# frontplatine_v0_1.net
KiCad netlist of a schematic drawn in EAGLE
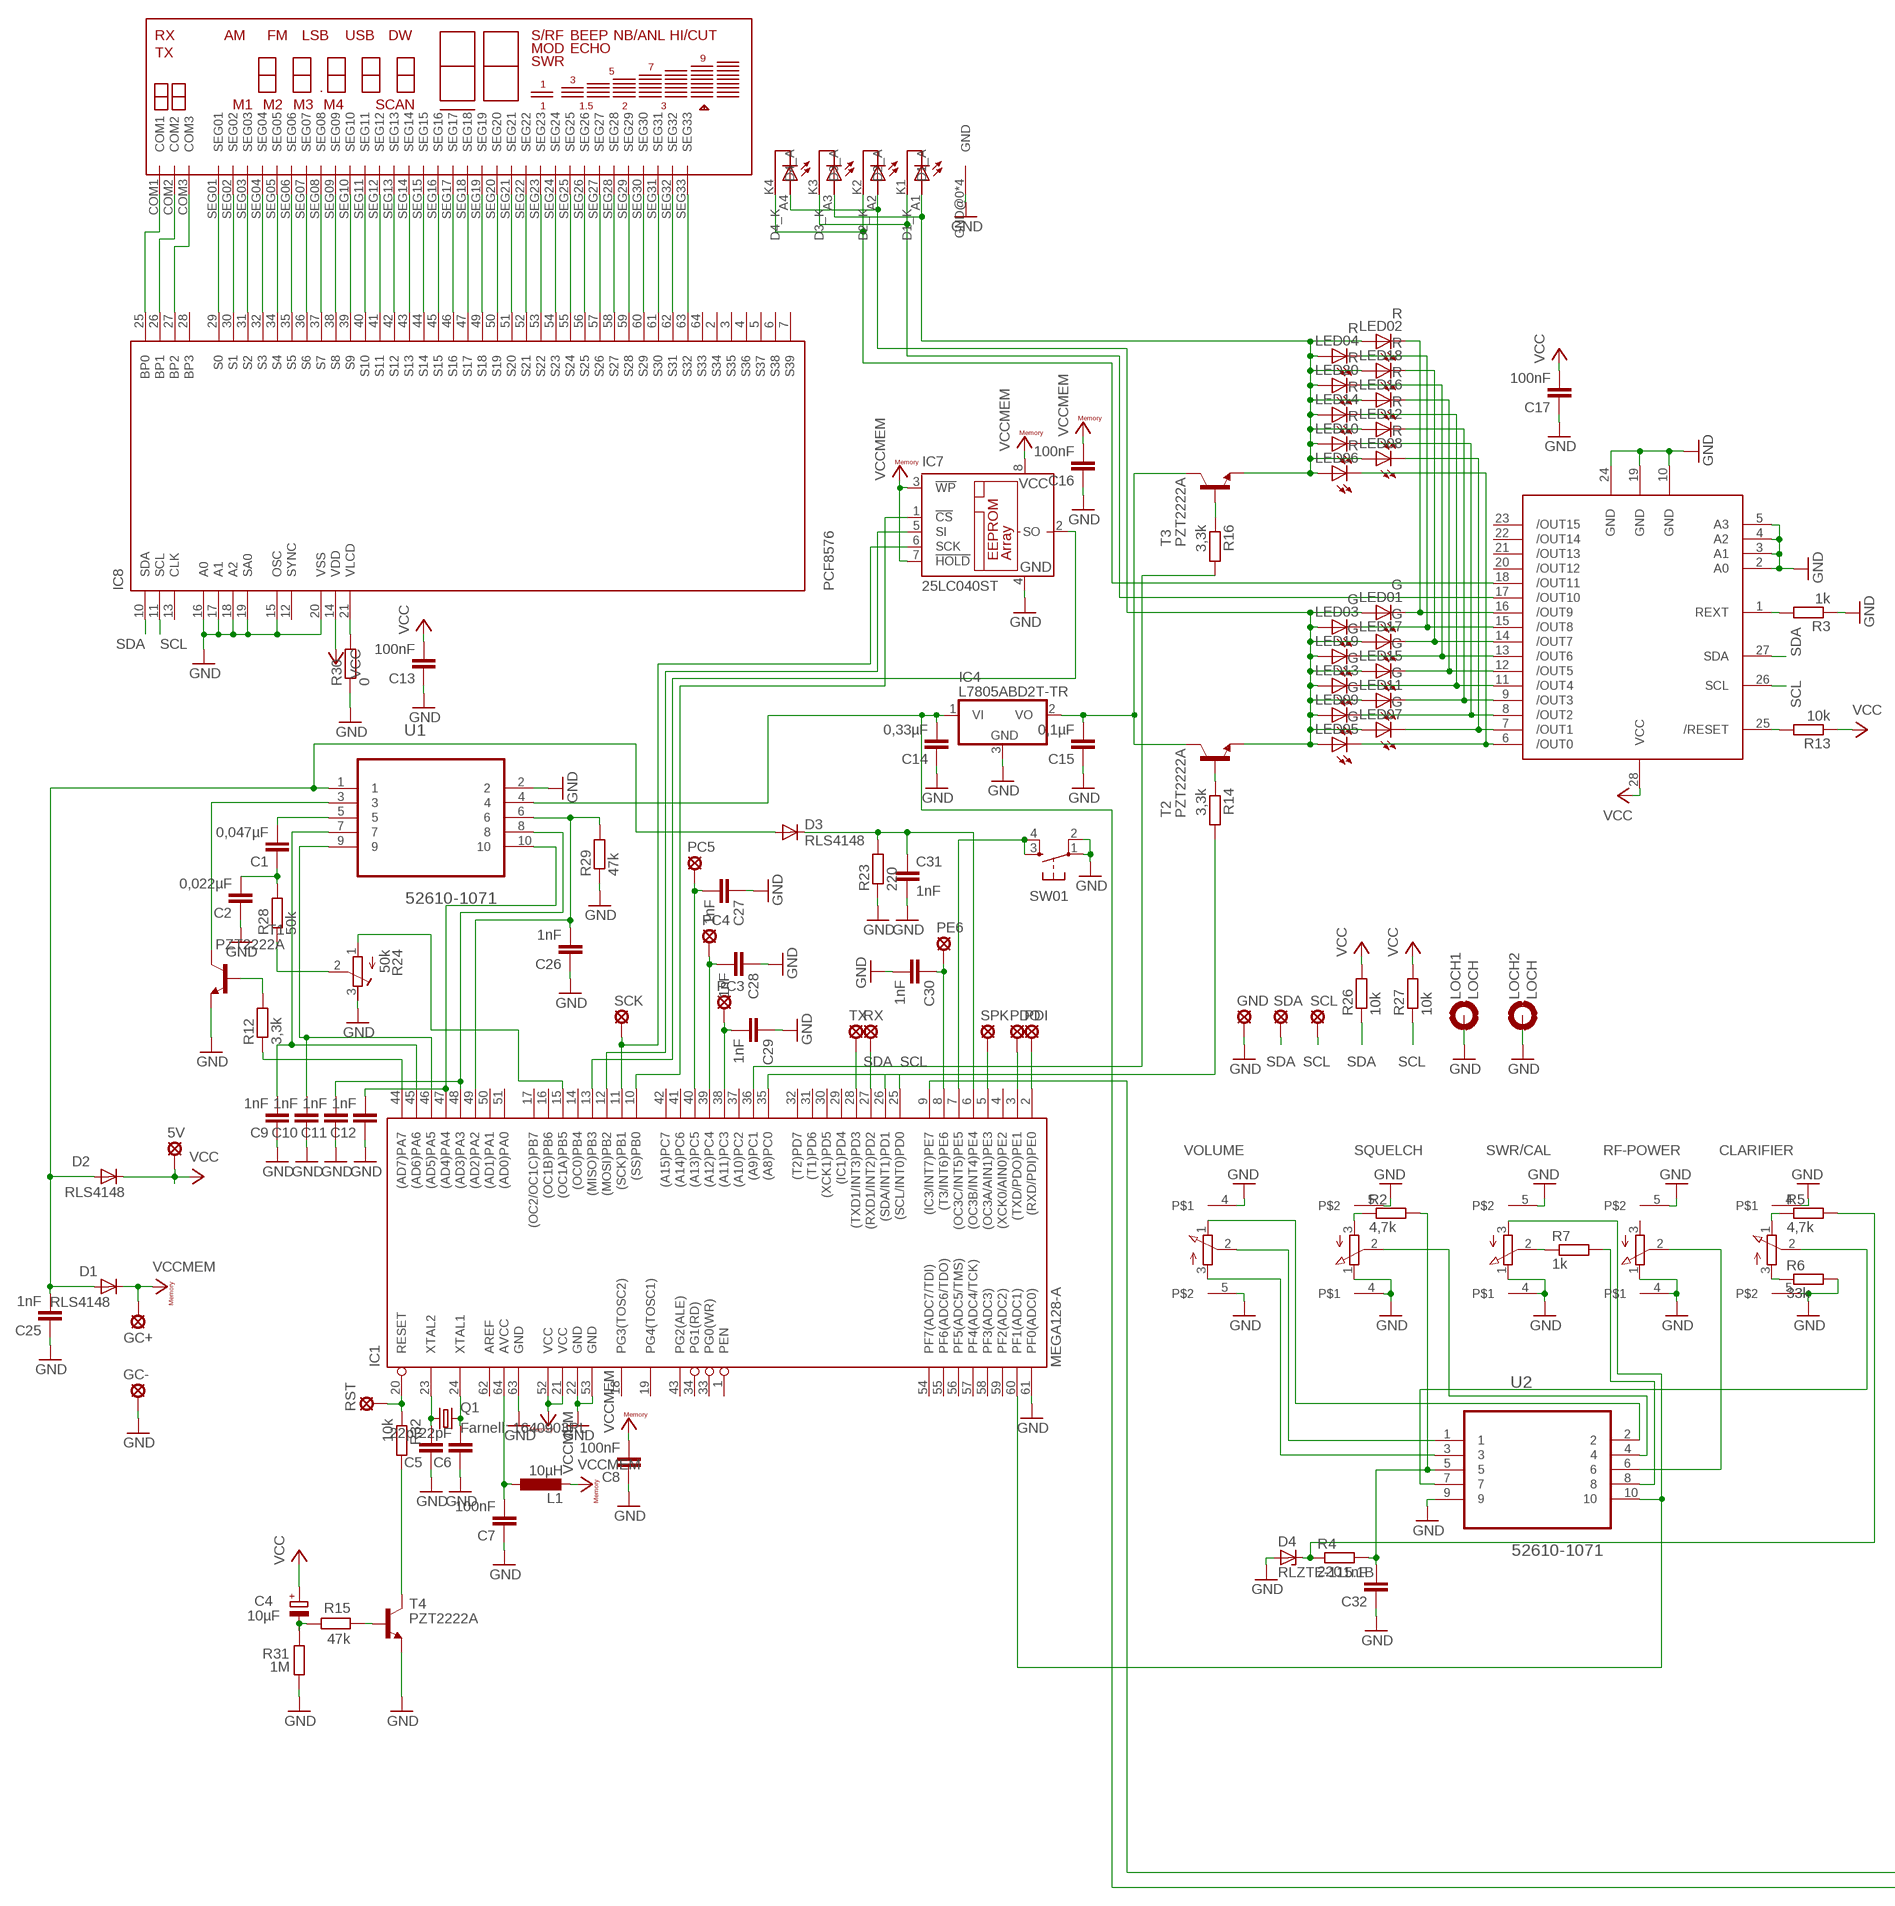
[diagram p0: schematic, sheet 1, part 1 of 2]
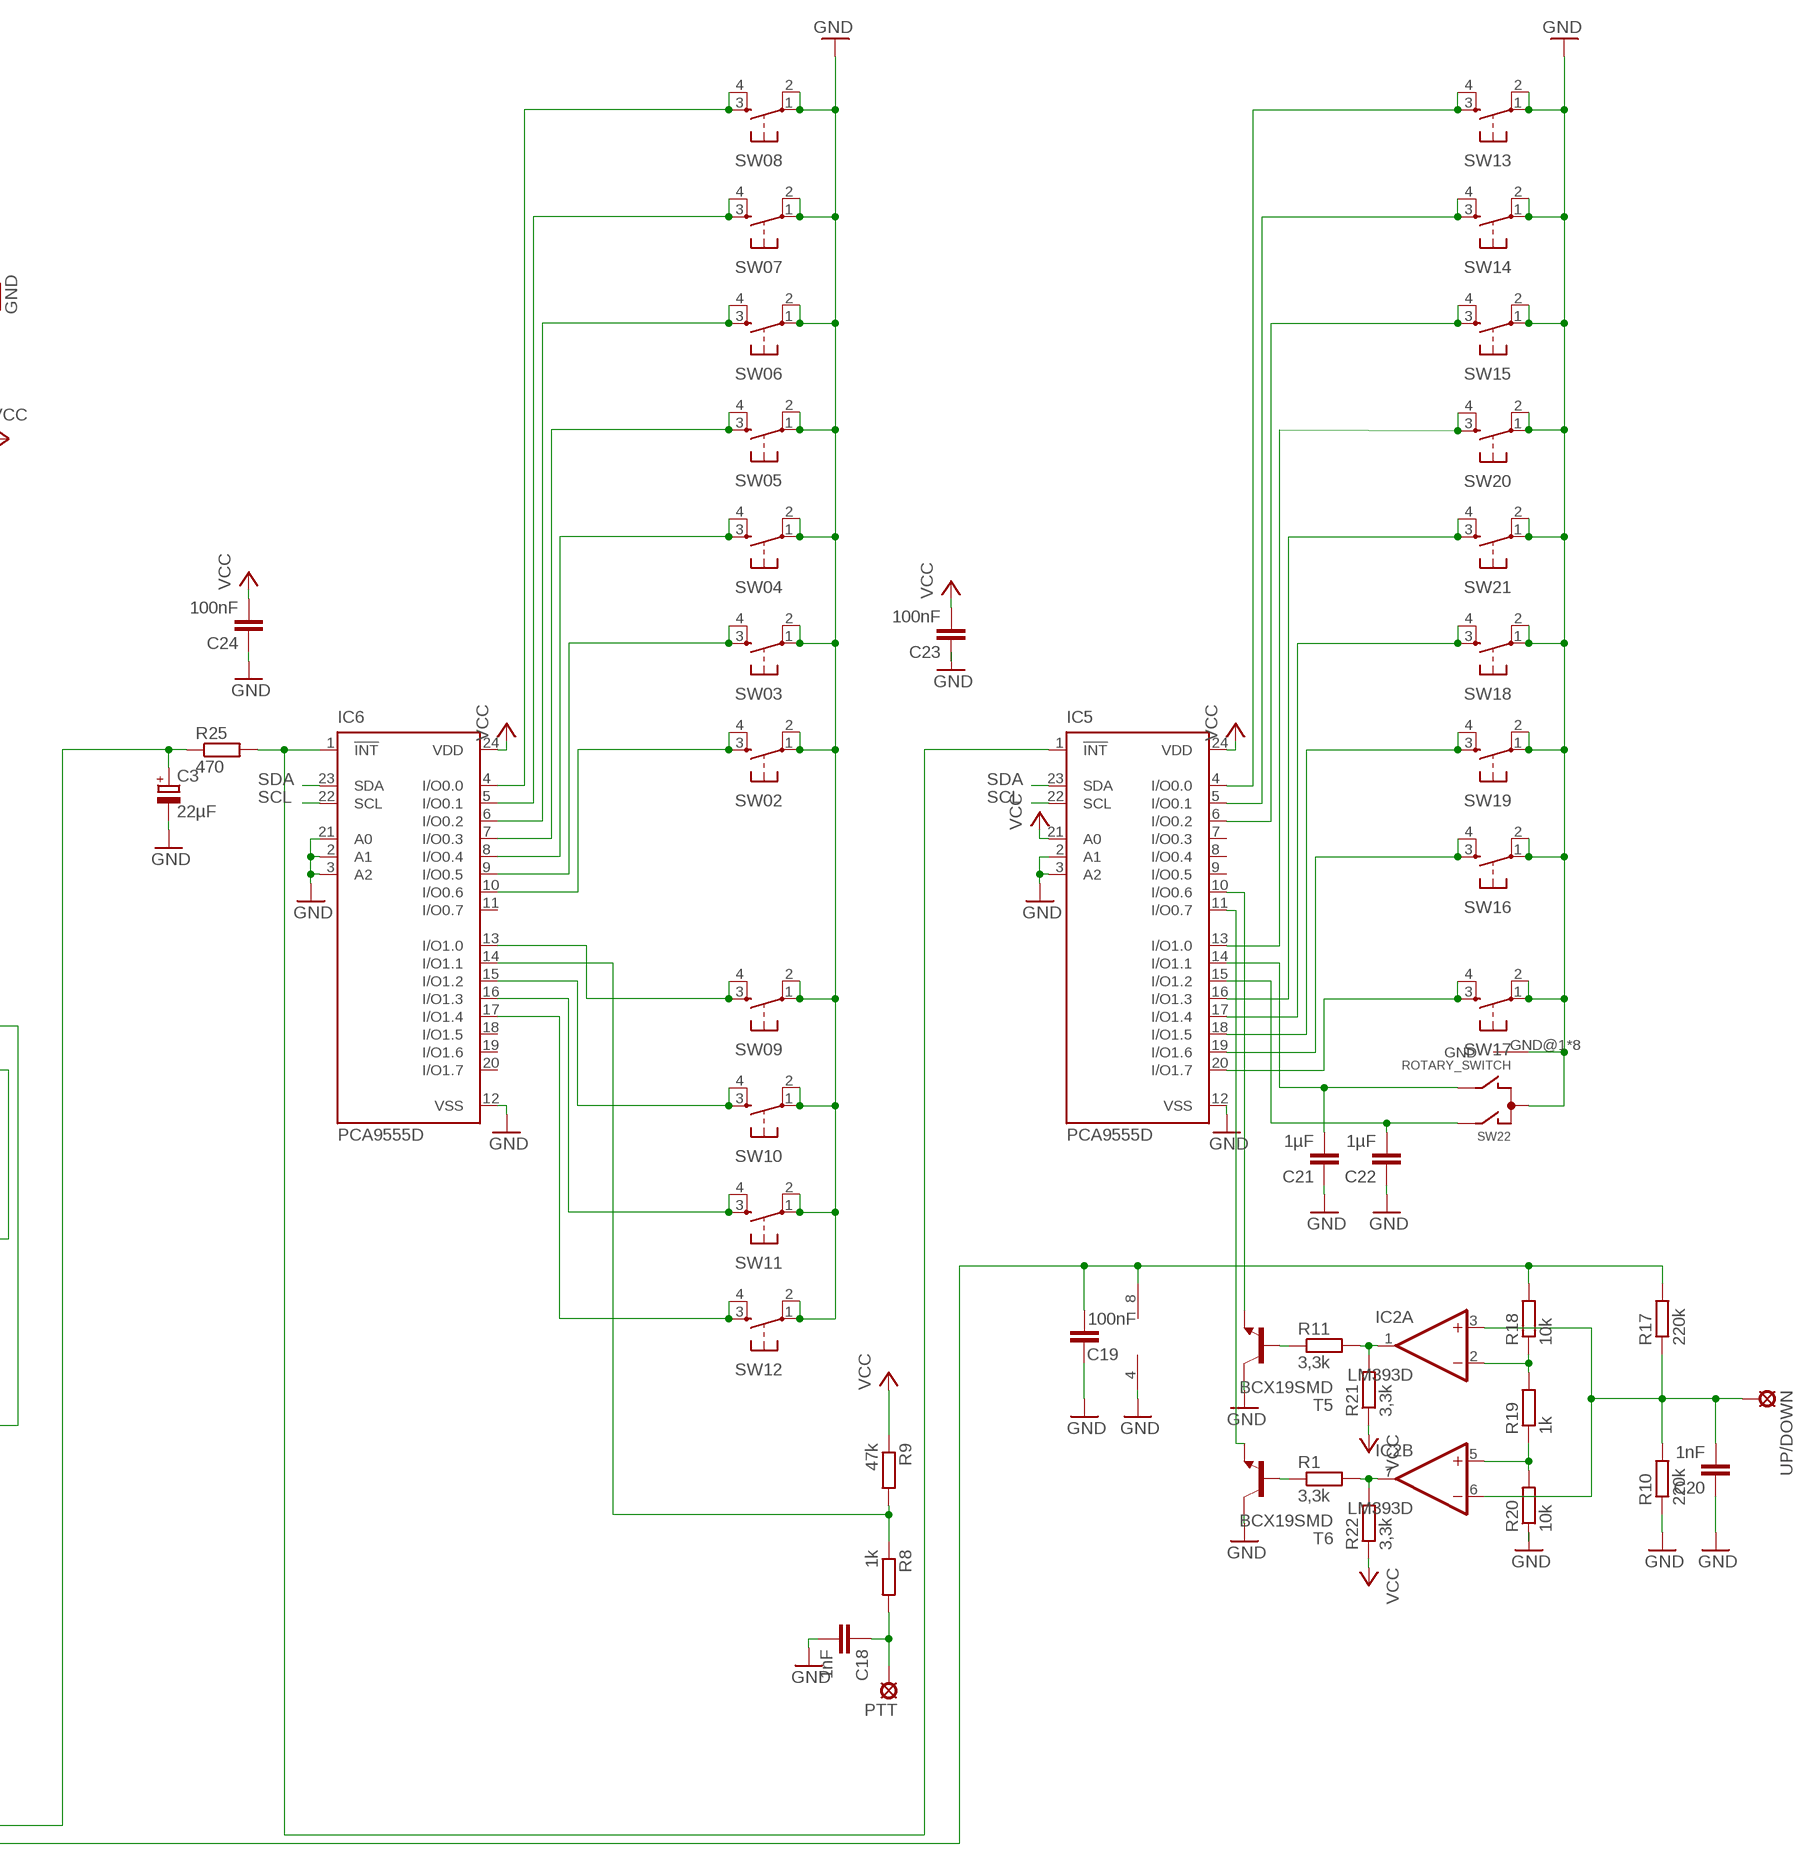
[diagram p1: schematic, sheet 1, part 2 of 2]

(export (version "E")
  (design (tool "Eeschema 10.0.6"))
  (components
    (comp (ref "5V")
      (value "SE11")
      (footprint "eagle-import:SE11")
      (libsource (lib "eagle-import") (part "SE11"))
    )
    (comp (ref "C1")
      (value "0,047µF")
      (footprint "eagle-import:C1206")
      (libsource (lib "eagle-import") (part "C-EUC1206"))
    )
    (comp (ref "C2")
      (value "0,022µF")
      (footprint "eagle-import:C1206")
      (libsource (lib "eagle-import") (part "resistor_C-EUC1206"))
    )
    (comp (ref "C3")
      (value "22µF")
      (footprint "eagle-import:CT3216")
      (libsource (lib "eagle-import") (part "CPOL-EUCT3216"))
    )
    (comp (ref "C4")
      (value "10µF")
      (footprint "eagle-import:CT3216")
      (libsource (lib "eagle-import") (part "CPOL-EUCT3216"))
    )
    (comp (ref "C5")
      (value "22pF")
      (footprint "eagle-import:C1206")
      (libsource (lib "eagle-import") (part "resistor_C-EUC1206"))
    )
    (comp (ref "C6")
      (value "22pF")
      (footprint "eagle-import:C1206")
      (libsource (lib "eagle-import") (part "resistor_C-EUC1206"))
    )
    (comp (ref "C7")
      (value "100nF")
      (footprint "eagle-import:C1206")
      (libsource (lib "eagle-import") (part "resistor_C-EUC1206"))
    )
    (comp (ref "C8")
      (value "100nF")
      (footprint "eagle-import:C1206")
      (libsource (lib "eagle-import") (part "resistor_C-EUC1206"))
    )
    (comp (ref "C9")
      (value "1nF")
      (footprint "eagle-import:C1206")
      (libsource (lib "eagle-import") (part "resistor_C-EUC1206"))
    )
    (comp (ref "C10")
      (value "1nF")
      (footprint "eagle-import:C1206")
      (libsource (lib "eagle-import") (part "resistor_C-EUC1206"))
    )
    (comp (ref "C11")
      (value "1nF")
      (footprint "eagle-import:C1206")
      (libsource (lib "eagle-import") (part "resistor_C-EUC1206"))
    )
    (comp (ref "C12")
      (value "1nF")
      (footprint "eagle-import:C1206")
      (libsource (lib "eagle-import") (part "resistor_C-EUC1206"))
    )
    (comp (ref "C13")
      (value "100nF")
      (footprint "eagle-import:C1206")
      (libsource (lib "eagle-import") (part "resistor_C-EUC1206"))
    )
    (comp (ref "C14")
      (value "0,33µF")
      (footprint "eagle-import:C1206")
      (libsource (lib "eagle-import") (part "resistor_C-EUC1206"))
    )
    (comp (ref "C15")
      (value "0,1µF")
      (footprint "eagle-import:C1206")
      (libsource (lib "eagle-import") (part "resistor_C-EUC1206"))
    )
    (comp (ref "C16")
      (value "100nF")
      (footprint "eagle-import:C1206")
      (libsource (lib "eagle-import") (part "resistor_C-EUC1206"))
    )
    (comp (ref "C17")
      (value "100nF")
      (footprint "eagle-import:C1206")
      (libsource (lib "eagle-import") (part "resistor_C-EUC1206"))
    )
    (comp (ref "C18")
      (value "1nF")
      (footprint "eagle-import:C1206")
      (libsource (lib "eagle-import") (part "resistor_C-EUC1206"))
    )
    (comp (ref "C19")
      (value "100nF")
      (footprint "eagle-import:C1206")
      (libsource (lib "eagle-import") (part "resistor_C-EUC1206"))
    )
    (comp (ref "C20")
      (value "1nF")
      (footprint "eagle-import:C1206")
      (libsource (lib "eagle-import") (part "resistor_C-EUC1206"))
    )
    (comp (ref "C21")
      (value "1µF")
      (footprint "eagle-import:C1206")
      (libsource (lib "eagle-import") (part "resistor_C-EUC1206"))
    )
    (comp (ref "C22")
      (value "1µF")
      (footprint "eagle-import:C1206")
      (libsource (lib "eagle-import") (part "resistor_C-EUC1206"))
    )
    (comp (ref "C23")
      (value "100nF")
      (footprint "eagle-import:C1206")
      (libsource (lib "eagle-import") (part "resistor_C-EUC1206"))
    )
    (comp (ref "C24")
      (value "100nF")
      (footprint "eagle-import:C1206")
      (libsource (lib "eagle-import") (part "resistor_C-EUC1206"))
    )
    (comp (ref "C25")
      (value "1nF")
      (footprint "eagle-import:C1206")
      (libsource (lib "eagle-import") (part "resistor_C-EUC1206"))
    )
    (comp (ref "C26")
      (value "1nF")
      (footprint "eagle-import:C1206")
      (libsource (lib "eagle-import") (part "resistor_C-EUC1206"))
    )
    (comp (ref "C27")
      (value "1nF")
      (footprint "eagle-import:C1206")
      (libsource (lib "eagle-import") (part "resistor_C-EUC1206"))
    )
    (comp (ref "C28")
      (value "1nF")
      (footprint "eagle-import:C1206")
      (libsource (lib "eagle-import") (part "resistor_C-EUC1206"))
    )
    (comp (ref "C29")
      (value "1nF")
      (footprint "eagle-import:C1206")
      (libsource (lib "eagle-import") (part "resistor_C-EUC1206"))
    )
    (comp (ref "C30")
      (value "1nF")
      (footprint "eagle-import:C1206")
      (libsource (lib "eagle-import") (part "resistor_C-EUC1206"))
    )
    (comp (ref "C31")
      (value "1nF")
      (footprint "eagle-import:C1206")
      (libsource (lib "eagle-import") (part "resistor_C-EUC1206"))
    )
    (comp (ref "C32")
      (value "1nF")
      (footprint "eagle-import:C1206")
      (libsource (lib "eagle-import") (part "resistor_C-EUC1206"))
    )
    (comp (ref "CLARIFIER")
      (value "POTI")
      (footprint "eagle-import:POTI")
      (libsource (lib "eagle-import") (part "POTI"))
    )
    (comp (ref "D1")
      (value "RLS4148")
      (footprint "eagle-import:SOD80C")
      (libsource (lib "eagle-import") (part "DIODE-SOD80C"))
    )
    (comp (ref "D2")
      (value "RLS4148")
      (footprint "eagle-import:SOD80C")
      (libsource (lib "eagle-import") (part "DIODE-SOD80C"))
    )
    (comp (ref "D3")
      (value "RLS4148")
      (footprint "eagle-import:SOD80C")
      (libsource (lib "eagle-import") (part "DIODE-SOD80C"))
    )
    (comp (ref "D4")
      (value "RLZTE-115.1B")
      (footprint "eagle-import:SOD80C")
      (libsource (lib "eagle-import") (part "ZENER-DIODESOD80C"))
    )
    (comp (ref "DISPLAY1")
      (value "DISPLAY")
      (footprint "eagle-import:DISPLAY")
      (libsource (lib "eagle-import") (part "DISPLAY"))
    )
    (comp (ref "GC+")
      (value "SE11")
      (footprint "eagle-import:SE11")
      (libsource (lib "eagle-import") (part "SE11"))
    )
    (comp (ref "GC-")
      (value "SE11")
      (footprint "eagle-import:SE11")
      (libsource (lib "eagle-import") (part "SE11"))
    )
    (comp (ref "GND")
      (value "SE11")
      (footprint "eagle-import:SE11")
      (libsource (lib "eagle-import") (part "SE11"))
    )
    (comp (ref "IC1")
      (value "MEGA128-A")
      (footprint "eagle-import:TQFP64")
      (fields (field (name "MPN") "ATMEGA128-16AU"))
      (libsource (lib "eagle-import") (part "MEGA128-A"))
    )
    (comp (ref "IC2")
      (value "LM393D")
      (footprint "eagle-import:SO08")
      (libsource (lib "eagle-import") (part "LM393D"))
    )
    (comp (ref "IC3")
      (value "TLC59116")
      (footprint "eagle-import:TSSOP28")
      (libsource (lib "eagle-import") (part "TLC59116"))
    )
    (comp (ref "IC4")
      (value "L7805ABD2T-TR")
      (footprint "eagle-import:TO252")
      (libsource (lib "eagle-import") (part "78DT05"))
    )
    (comp (ref "IC5")
      (value "PCA9555D")
      (footprint "eagle-import:SO24")
      (fields (field (name "MPN") "PCA9555DW"))
      (libsource (lib "eagle-import") (part "PCA9555D"))
    )
    (comp (ref "IC6")
      (value "PCA9555D")
      (footprint "eagle-import:SO24")
      (fields (field (name "MPN") "PCA9555DW"))
      (libsource (lib "eagle-import") (part "PCA9555D"))
    )
    (comp (ref "IC7")
      (value "25LC040ST")
      (footprint "eagle-import:TSSOP8")
      (fields (field (name "MF") "MICROCHIP") (field (name "MPN") "25LC040A-I/ST"))
      (libsource (lib "eagle-import") (part "25STLC040"))
    )
    (comp (ref "IC8")
      (value "PCF8576")
      (footprint "eagle-import:64LQFP")
      (libsource (lib "eagle-import") (part "PCF8576"))
    )
    (comp (ref "L1")
      (value "10µH")
      (footprint "eagle-import:L1812")
      (libsource (lib "eagle-import") (part "L-EUL1812"))
    )
    (comp (ref "LED01")
      (value "G")
      (footprint "eagle-import:CHIPLED_1206")
      (libsource (lib "eagle-import") (part "LEDCHIPLED_1206"))
    )
    (comp (ref "LED02")
      (value "R")
      (footprint "eagle-import:CHIPLED_1206")
      (libsource (lib "eagle-import") (part "LEDCHIPLED_1206"))
    )
    (comp (ref "LED03")
      (value "G")
      (footprint "eagle-import:CHIPLED_1206")
      (libsource (lib "eagle-import") (part "LEDCHIPLED_1206"))
    )
    (comp (ref "LED04")
      (value "R")
      (footprint "eagle-import:CHIPLED_1206")
      (libsource (lib "eagle-import") (part "LEDCHIPLED_1206"))
    )
    (comp (ref "LED05")
      (value "G")
      (footprint "eagle-import:CHIPLED_1206")
      (libsource (lib "eagle-import") (part "LEDCHIPLED_1206"))
    )
    (comp (ref "LED06")
      (value "R")
      (footprint "eagle-import:CHIPLED_1206")
      (libsource (lib "eagle-import") (part "LEDCHIPLED_1206"))
    )
    (comp (ref "LED07")
      (value "G")
      (footprint "eagle-import:CHIPLED_1206")
      (libsource (lib "eagle-import") (part "LEDCHIPLED_1206"))
    )
    (comp (ref "LED08")
      (value "R")
      (footprint "eagle-import:CHIPLED_1206")
      (libsource (lib "eagle-import") (part "LEDCHIPLED_1206"))
    )
    (comp (ref "LED09")
      (value "G")
      (footprint "eagle-import:CHIPLED_1206")
      (libsource (lib "eagle-import") (part "LEDCHIPLED_1206"))
    )
    (comp (ref "LED10")
      (value "R")
      (footprint "eagle-import:CHIPLED_1206")
      (libsource (lib "eagle-import") (part "LEDCHIPLED_1206"))
    )
    (comp (ref "LED11")
      (value "G")
      (footprint "eagle-import:CHIPLED_1206")
      (libsource (lib "eagle-import") (part "LEDCHIPLED_1206"))
    )
    (comp (ref "LED12")
      (value "R")
      (footprint "eagle-import:CHIPLED_1206")
      (libsource (lib "eagle-import") (part "LEDCHIPLED_1206"))
    )
    (comp (ref "LED13")
      (value "G")
      (footprint "eagle-import:CHIPLED_1206")
      (libsource (lib "eagle-import") (part "LEDCHIPLED_1206"))
    )
    (comp (ref "LED14")
      (value "R")
      (footprint "eagle-import:CHIPLED_1206")
      (libsource (lib "eagle-import") (part "LEDCHIPLED_1206"))
    )
    (comp (ref "LED15")
      (value "G")
      (footprint "eagle-import:CHIPLED_1206")
      (libsource (lib "eagle-import") (part "LEDCHIPLED_1206"))
    )
    (comp (ref "LED16")
      (value "R")
      (footprint "eagle-import:CHIPLED_1206")
      (libsource (lib "eagle-import") (part "LEDCHIPLED_1206"))
    )
    (comp (ref "LED17")
      (value "G")
      (footprint "eagle-import:CHIPLED_1206")
      (libsource (lib "eagle-import") (part "LEDCHIPLED_1206"))
    )
    (comp (ref "LED18")
      (value "R")
      (footprint "eagle-import:CHIPLED_1206")
      (libsource (lib "eagle-import") (part "LEDCHIPLED_1206"))
    )
    (comp (ref "LED19")
      (value "G")
      (footprint "eagle-import:CHIPLED_1206")
      (libsource (lib "eagle-import") (part "LEDCHIPLED_1206"))
    )
    (comp (ref "LED20")
      (value "R")
      (footprint "eagle-import:CHIPLED_1206")
      (libsource (lib "eagle-import") (part "LEDCHIPLED_1206"))
    )
    (comp (ref "LOCH1")
      (value "LOCH")
      (footprint "eagle-import:LOCH")
      (libsource (lib "eagle-import") (part "LOCH"))
    )
    (comp (ref "LOCH2")
      (value "LOCH")
      (footprint "eagle-import:LOCH")
      (libsource (lib "eagle-import") (part "LOCH"))
    )
    (comp (ref "PC3")
      (value "SE11")
      (footprint "eagle-import:SE11")
      (libsource (lib "eagle-import") (part "SE11"))
    )
    (comp (ref "PC4")
      (value "SE11")
      (footprint "eagle-import:SE11")
      (libsource (lib "eagle-import") (part "SE11"))
    )
    (comp (ref "PC5")
      (value "SE11")
      (footprint "eagle-import:SE11")
      (libsource (lib "eagle-import") (part "SE11"))
    )
    (comp (ref "PDI")
      (value "SE11")
      (footprint "eagle-import:SE11")
      (libsource (lib "eagle-import") (part "SE11"))
    )
    (comp (ref "PDO")
      (value "SE11")
      (footprint "eagle-import:SE11")
      (libsource (lib "eagle-import") (part "SE11"))
    )
    (comp (ref "PE6")
      (value "SE11")
      (footprint "eagle-import:SE11")
      (libsource (lib "eagle-import") (part "SE11"))
    )
    (comp (ref "PTT")
      (value "SE11")
      (footprint "eagle-import:SE11")
      (libsource (lib "eagle-import") (part "SE11"))
    )
    (comp (ref "Q1")
      (value "Farnell: 1640903RL")
      (footprint "eagle-import:HC49UP")
      (libsource (lib "eagle-import") (part "CRYSTALHC49UP"))
    )
    (comp (ref "R1")
      (value "3,3k")
      (footprint "eagle-import:R1206")
      (libsource (lib "eagle-import") (part "resistor_R-EU_R1206"))
    )
    (comp (ref "R2")
      (value "4,7k")
      (footprint "eagle-import:R1206")
      (libsource (lib "eagle-import") (part "resistor_R-EU_R1206"))
    )
    (comp (ref "R3")
      (value "1k")
      (footprint "eagle-import:R1206")
      (libsource (lib "eagle-import") (part "R-EU_R1206"))
    )
    (comp (ref "R4")
      (value "220")
      (footprint "eagle-import:R1206")
      (libsource (lib "eagle-import") (part "resistor_R-EU_R1206"))
    )
    (comp (ref "R5")
      (value "4,7k")
      (footprint "eagle-import:R1206")
      (libsource (lib "eagle-import") (part "resistor_R-EU_R1206"))
    )
    (comp (ref "R6")
      (value "33k")
      (footprint "eagle-import:R1206")
      (libsource (lib "eagle-import") (part "resistor_R-EU_R1206"))
    )
    (comp (ref "R7")
      (value "1k")
      (footprint "eagle-import:R1206")
      (libsource (lib "eagle-import") (part "resistor_R-EU_R1206"))
    )
    (comp (ref "R8")
      (value "1k")
      (footprint "eagle-import:R1206")
      (libsource (lib "eagle-import") (part "resistor_R-EU_R1206"))
    )
    (comp (ref "R9")
      (value "47k")
      (footprint "eagle-import:R1206")
      (libsource (lib "eagle-import") (part "resistor_R-EU_R1206"))
    )
    (comp (ref "R10")
      (value "220k")
      (footprint "eagle-import:R1206")
      (libsource (lib "eagle-import") (part "resistor_R-EU_R1206"))
    )
    (comp (ref "R11")
      (value "3,3k")
      (footprint "eagle-import:R1206")
      (libsource (lib "eagle-import") (part "resistor_R-EU_R1206"))
    )
    (comp (ref "R12")
      (value "3,3k")
      (footprint "eagle-import:R1206")
      (libsource (lib "eagle-import") (part "resistor_R-EU_R1206"))
    )
    (comp (ref "R13")
      (value "10k")
      (footprint "eagle-import:R1206")
      (libsource (lib "eagle-import") (part "resistor_R-EU_R1206"))
    )
    (comp (ref "R14")
      (value "3,3k")
      (footprint "eagle-import:R1206")
      (libsource (lib "eagle-import") (part "resistor_R-EU_R1206"))
    )
    (comp (ref "R15")
      (value "47k")
      (footprint "eagle-import:R1206")
      (libsource (lib "eagle-import") (part "resistor_R-EU_R1206"))
    )
    (comp (ref "R16")
      (value "3,3k")
      (footprint "eagle-import:R1206")
      (libsource (lib "eagle-import") (part "resistor_R-EU_R1206"))
    )
    (comp (ref "R17")
      (value "220k")
      (footprint "eagle-import:R1206")
      (libsource (lib "eagle-import") (part "resistor_R-EU_R1206"))
    )
    (comp (ref "R18")
      (value "10k")
      (footprint "eagle-import:R1206")
      (libsource (lib "eagle-import") (part "resistor_R-EU_R1206"))
    )
    (comp (ref "R19")
      (value "1k")
      (footprint "eagle-import:R1206")
      (libsource (lib "eagle-import") (part "resistor_R-EU_R1206"))
    )
    (comp (ref "R20")
      (value "10k")
      (footprint "eagle-import:R1206")
      (libsource (lib "eagle-import") (part "resistor_R-EU_R1206"))
    )
    (comp (ref "R21")
      (value "3,3k")
      (footprint "eagle-import:R1206")
      (libsource (lib "eagle-import") (part "resistor_R-EU_R1206"))
    )
    (comp (ref "R22")
      (value "3,3k")
      (footprint "eagle-import:R1206")
      (libsource (lib "eagle-import") (part "resistor_R-EU_R1206"))
    )
    (comp (ref "R23")
      (value "220")
      (footprint "eagle-import:R1206")
      (libsource (lib "eagle-import") (part "resistor_R-EU_R1206"))
    )
    (comp (ref "R24")
      (value "50k")
      (footprint "eagle-import:RTRIM3314J")
      (libsource (lib "eagle-import") (part "R-TRIMM3314J"))
    )
    (comp (ref "R25")
      (value "470")
      (footprint "eagle-import:R1206")
      (libsource (lib "eagle-import") (part "resistor_R-EU_R1206"))
    )
    (comp (ref "R26")
      (value "10k")
      (footprint "eagle-import:R1206")
      (libsource (lib "eagle-import") (part "resistor_R-EU_R1206"))
    )
    (comp (ref "R27")
      (value "10k")
      (footprint "eagle-import:R1206")
      (libsource (lib "eagle-import") (part "resistor_R-EU_R1206"))
    )
    (comp (ref "R28")
      (value "50k")
      (footprint "eagle-import:R1206")
      (libsource (lib "eagle-import") (part "resistor_R-EU_R1206"))
    )
    (comp (ref "R29")
      (value "47k")
      (footprint "eagle-import:R1206")
      (libsource (lib "eagle-import") (part "resistor_R-EU_R1206"))
    )
    (comp (ref "R30")
      (value "0")
      (footprint "eagle-import:R1206")
      (libsource (lib "eagle-import") (part "resistor_R-EU_R1206"))
    )
    (comp (ref "R31")
      (value "1M")
      (footprint "eagle-import:R1206")
      (libsource (lib "eagle-import") (part "resistor_R-EU_R1206"))
    )
    (comp (ref "R32")
      (value "10k")
      (footprint "eagle-import:R1206")
      (libsource (lib "eagle-import") (part "resistor_R-EU_R1206"))
    )
    (comp (ref "RF-POWER")
      (value "POTI")
      (footprint "eagle-import:POTI")
      (libsource (lib "eagle-import") (part "POTI"))
    )
    (comp (ref "RST")
      (value "SE11")
      (footprint "eagle-import:SE11")
      (libsource (lib "eagle-import") (part "SE11"))
    )
    (comp (ref "RX")
      (value "SE11")
      (footprint "eagle-import:SE11")
      (libsource (lib "eagle-import") (part "SE11"))
    )
    (comp (ref "SCK")
      (value "SE11")
      (footprint "eagle-import:SE11")
      (libsource (lib "eagle-import") (part "SE11"))
    )
    (comp (ref "SCL")
      (value "SE11")
      (footprint "eagle-import:SE11")
      (libsource (lib "eagle-import") (part "SE11"))
    )
    (comp (ref "SDA")
      (value "SE11")
      (footprint "eagle-import:SE11")
      (libsource (lib "eagle-import") (part "SE11"))
    )
    (comp (ref "SPK")
      (value "SE11")
      (footprint "eagle-import:SE11")
      (libsource (lib "eagle-import") (part "SE11"))
    )
    (comp (ref "SQUELCH")
      (value "POTI")
      (footprint "eagle-import:POTI")
      (libsource (lib "eagle-import") (part "POTI"))
    )
    (comp (ref "SW01")
      (value "TASTER")
      (footprint "eagle-import:TASTER")
      (libsource (lib "eagle-import") (part "TASTER"))
    )
    (comp (ref "SW02")
      (value "TASTER")
      (footprint "eagle-import:TASTER")
      (libsource (lib "eagle-import") (part "TASTER"))
    )
    (comp (ref "SW03")
      (value "TASTER")
      (footprint "eagle-import:TASTER")
      (libsource (lib "eagle-import") (part "TASTER"))
    )
    (comp (ref "SW04")
      (value "TASTER")
      (footprint "eagle-import:TASTER")
      (libsource (lib "eagle-import") (part "TASTER"))
    )
    (comp (ref "SW05")
      (value "TASTER")
      (footprint "eagle-import:TASTER")
      (libsource (lib "eagle-import") (part "TASTER"))
    )
    (comp (ref "SW06")
      (value "TASTER")
      (footprint "eagle-import:TASTER")
      (libsource (lib "eagle-import") (part "TASTER"))
    )
    (comp (ref "SW07")
      (value "TASTER")
      (footprint "eagle-import:TASTER")
      (libsource (lib "eagle-import") (part "TASTER"))
    )
    (comp (ref "SW08")
      (value "TASTER")
      (footprint "eagle-import:TASTER")
      (libsource (lib "eagle-import") (part "TASTER"))
    )
    (comp (ref "SW09")
      (value "TASTER")
      (footprint "eagle-import:TASTER")
      (libsource (lib "eagle-import") (part "TASTER"))
    )
    (comp (ref "SW10")
      (value "TASTER")
      (footprint "eagle-import:TASTER")
      (libsource (lib "eagle-import") (part "TASTER"))
    )
    (comp (ref "SW11")
      (value "TASTER")
      (footprint "eagle-import:TASTER")
      (libsource (lib "eagle-import") (part "TASTER"))
    )
    (comp (ref "SW12")
      (value "TASTER")
      (footprint "eagle-import:TASTER")
      (libsource (lib "eagle-import") (part "TASTER"))
    )
    (comp (ref "SW13")
      (value "TASTER")
      (footprint "eagle-import:TASTER")
      (libsource (lib "eagle-import") (part "TASTER"))
    )
    (comp (ref "SW14")
      (value "TASTER")
      (footprint "eagle-import:TASTER")
      (libsource (lib "eagle-import") (part "TASTER"))
    )
    (comp (ref "SW15")
      (value "TASTER")
      (footprint "eagle-import:TASTER")
      (libsource (lib "eagle-import") (part "TASTER"))
    )
    (comp (ref "SW16")
      (value "TASTER")
      (footprint "eagle-import:TASTER")
      (libsource (lib "eagle-import") (part "TASTER"))
    )
    (comp (ref "SW17")
      (value "TASTER")
      (footprint "eagle-import:TASTER")
      (libsource (lib "eagle-import") (part "TASTER"))
    )
    (comp (ref "SW18")
      (value "TASTER")
      (footprint "eagle-import:TASTER")
      (libsource (lib "eagle-import") (part "TASTER"))
    )
    (comp (ref "SW19")
      (value "TASTER")
      (footprint "eagle-import:TASTER")
      (libsource (lib "eagle-import") (part "TASTER"))
    )
    (comp (ref "SW20")
      (value "TASTER")
      (footprint "eagle-import:TASTER")
      (libsource (lib "eagle-import") (part "TASTER"))
    )
    (comp (ref "SW21")
      (value "TASTER")
      (footprint "eagle-import:TASTER")
      (libsource (lib "eagle-import") (part "TASTER"))
    )
    (comp (ref "SW22")
      (value "ROTARY_SWITCH")
      (footprint "eagle-import:ROTARY_SWITCH")
      (libsource (lib "eagle-import") (part "ROTARY_SWITCH"))
    )
    (comp (ref "SWR/CAL")
      (value "POTI")
      (footprint "eagle-import:POTI")
      (libsource (lib "eagle-import") (part "POTI"))
    )
    (comp (ref "T1")
      (value "PZT2222A")
      (footprint "eagle-import:SOT223")
      (libsource (lib "eagle-import") (part "-NPN-SOT223PZT2222A"))
    )
    (comp (ref "T2")
      (value "PZT2222A")
      (footprint "eagle-import:SOT223")
      (libsource (lib "eagle-import") (part "-NPN-SOT223PZT2222A"))
    )
    (comp (ref "T3")
      (value "PZT2222A")
      (footprint "eagle-import:SOT223")
      (libsource (lib "eagle-import") (part "-NPN-SOT223PZT2222A"))
    )
    (comp (ref "T4")
      (value "PZT2222A")
      (footprint "eagle-import:SOT223")
      (libsource (lib "eagle-import") (part "-NPN-SOT223PZT2222A"))
    )
    (comp (ref "T5")
      (value "BCX19SMD")
      (footprint "eagle-import:SOT23-BEC")
      (libsource (lib "eagle-import") (part "BCX19SMD"))
    )
    (comp (ref "T6")
      (value "BCX19SMD")
      (footprint "eagle-import:SOT23-BEC")
      (libsource (lib "eagle-import") (part "BCX19SMD"))
    )
    (comp (ref "TX")
      (value "SE11")
      (footprint "eagle-import:SE11")
      (libsource (lib "eagle-import") (part "SE11"))
    )
    (comp (ref "U1")
      (value "52610-1071")
      (footprint "eagle-import:MOLEX_52610-1071")
      (libsource (lib "eagle-import") (part "52610-1071"))
    )
    (comp (ref "U2")
      (value "52610-1071")
      (footprint "eagle-import:MOLEX_52610-1071")
      (libsource (lib "eagle-import") (part "52610-1071"))
    )
    (comp (ref "UP/DOWN")
      (value "SE11")
      (footprint "eagle-import:SE11")
      (libsource (lib "eagle-import") (part "SE11"))
    )
    (comp (ref "VOLUME")
      (value "POTI")
      (footprint "eagle-import:POTI")
      (libsource (lib "eagle-import") (part "POTI"))
    )
  )
  (nets
    (net (code "1") (name "/SCL") (class "Default")
      (node (ref "IC1") (pin "25") (pinfunction "(SCL/INT0)PD0_25") (pintype "bidirectional"))
      (node (ref "IC3") (pin "26") (pinfunction "SCL_26") (pintype "bidirectional"))
      (node (ref "IC5") (pin "22") (pinfunction "SCL_22") (pintype "input"))
      (node (ref "IC6") (pin "22") (pinfunction "SCL_22") (pintype "input"))
      (node (ref "IC8") (pin "11") (pinfunction "SCL_11") (pintype "input"))
      (node (ref "R27") (pin "1") (pinfunction "1_1") (pintype "passive"))
      (node (ref "SCL") (pin "MP") (pinfunction "MP_MP") (pintype "passive"))
    )
    (net (code "2") (name "/SDA") (class "Default")
      (node (ref "IC1") (pin "26") (pinfunction "(SDA/INT1)PD1_26") (pintype "bidirectional"))
      (node (ref "IC3") (pin "27") (pinfunction "SDA_27") (pintype "bidirectional"))
      (node (ref "IC5") (pin "23") (pinfunction "SDA_23") (pintype "bidirectional"))
      (node (ref "IC6") (pin "23") (pinfunction "SDA_23") (pintype "bidirectional"))
      (node (ref "IC8") (pin "10") (pinfunction "SDA_10") (pintype "bidirectional"))
      (node (ref "R26") (pin "1") (pinfunction "1_1") (pintype "passive"))
      (node (ref "SDA") (pin "MP") (pinfunction "MP_MP") (pintype "passive"))
    )
    (net (code "3") (name "GND") (class "Default")
      (node (ref "C10") (pin "1") (pinfunction "1_1") (pintype "passive"))
      (node (ref "C11") (pin "1") (pinfunction "1_1") (pintype "passive"))
      (node (ref "C12") (pin "1") (pinfunction "1_1") (pintype "passive"))
      (node (ref "C13") (pin "1") (pinfunction "1_1") (pintype "passive"))
      (node (ref "C14") (pin "1") (pinfunction "1_1") (pintype "passive"))
      (node (ref "C15") (pin "1") (pinfunction "1_1") (pintype "passive"))
      (node (ref "C16") (pin "1") (pinfunction "1_1") (pintype "passive"))
      (node (ref "C17") (pin "1") (pinfunction "1_1") (pintype "passive"))
      (node (ref "C18") (pin "2") (pinfunction "2_2") (pintype "passive"))
      (node (ref "C19") (pin "1") (pinfunction "1_1") (pintype "passive"))
      (node (ref "C2") (pin "1") (pinfunction "1_1") (pintype "passive"))
      (node (ref "C20") (pin "1") (pinfunction "1_1") (pintype "passive"))
      (node (ref "C21") (pin "1") (pinfunction "1_1") (pintype "passive"))
      (node (ref "C22") (pin "1") (pinfunction "1_1") (pintype "passive"))
      (node (ref "C23") (pin "1") (pinfunction "1_1") (pintype "passive"))
      (node (ref "C24") (pin "1") (pinfunction "1_1") (pintype "passive"))
      (node (ref "C25") (pin "1") (pinfunction "1_1") (pintype "passive"))
      (node (ref "C26") (pin "1") (pinfunction "1_1") (pintype "passive"))
      (node (ref "C27") (pin "1") (pinfunction "1_1") (pintype "passive"))
      (node (ref "C28") (pin "1") (pinfunction "1_1") (pintype "passive"))
      (node (ref "C29") (pin "1") (pinfunction "1_1") (pintype "passive"))
      (node (ref "C3") (pin "-") (pinfunction "-_-") (pintype "passive"))
      (node (ref "C30") (pin "2") (pinfunction "2_2") (pintype "passive"))
      (node (ref "C31") (pin "2") (pinfunction "2_2") (pintype "passive"))
      (node (ref "C32") (pin "1") (pinfunction "1_1") (pintype "passive"))
      (node (ref "C5") (pin "1") (pinfunction "1_1") (pintype "passive"))
      (node (ref "C6") (pin "1") (pinfunction "1_1") (pintype "passive"))
      (node (ref "C7") (pin "1") (pinfunction "1_1") (pintype "passive"))
      (node (ref "C8") (pin "1") (pinfunction "1_1") (pintype "passive"))
      (node (ref "C9") (pin "1") (pinfunction "1_1") (pintype "passive"))
      (node (ref "CLARIFIER") (pin "4") (pinfunction "P$1_4") (pintype "power_in"))
      (node (ref "CLARIFIER") (pin "5") (pinfunction "P$2_5") (pintype "power_in"))
      (node (ref "D4") (pin "A") (pinfunction "A_A") (pintype "passive"))
      (node (ref "DISPLAY1") (pin "GND@0") (pinfunction "GND_GND@0") (pintype "power_in"))
      (node (ref "DISPLAY1") (pin "GND@3") (pinfunction "GND_GND@3") (pintype "power_in"))
      (node (ref "DISPLAY1") (pin "GND@6") (pinfunction "GND_GND@6") (pintype "power_in"))
      (node (ref "DISPLAY1") (pin "GND@7") (pinfunction "GND_GND@7") (pintype "power_in"))
      (node (ref "GC-") (pin "MP") (pinfunction "MP_MP") (pintype "passive"))
      (node (ref "GND") (pin "MP") (pinfunction "MP_MP") (pintype "passive"))
      (node (ref "IC1") (pin "22") (pinfunction "GND_22") (pintype "power_in"))
      (node (ref "IC1") (pin "53") (pinfunction "GND_53") (pintype "power_in"))
      (node (ref "IC1") (pin "61") (pinfunction "PF0(ADC0)_61") (pintype "input"))
      (node (ref "IC1") (pin "63") (pinfunction "GND_63") (pintype "power_in"))
      (node (ref "IC2") (pin "4") (pinfunction "V-_4") (pintype "power_in"))
      (node (ref "IC3") (pin "10") (pinfunction "GND_10") (pintype "bidirectional"))
      (node (ref "IC3") (pin "19") (pinfunction "GND_19") (pintype "bidirectional"))
      (node (ref "IC3") (pin "2") (pinfunction "A0_2") (pintype "bidirectional"))
      (node (ref "IC3") (pin "24") (pinfunction "GND_24") (pintype "bidirectional"))
      (node (ref "IC3") (pin "3") (pinfunction "A1_3") (pintype "bidirectional"))
      (node (ref "IC3") (pin "4") (pinfunction "A2_4") (pintype "bidirectional"))
      (node (ref "IC3") (pin "5") (pinfunction "A3_5") (pintype "bidirectional"))
      (node (ref "IC4") (pin "3") (pinfunction "GND_3") (pintype "passive"))
      (node (ref "IC5") (pin "12") (pinfunction "VSS_12") (pintype "power_in"))
      (node (ref "IC5") (pin "2") (pinfunction "A1_2") (pintype "input"))
      (node (ref "IC5") (pin "3") (pinfunction "A2_3") (pintype "input"))
      (node (ref "IC6") (pin "12") (pinfunction "VSS_12") (pintype "power_in"))
      (node (ref "IC6") (pin "2") (pinfunction "A1_2") (pintype "input"))
      (node (ref "IC6") (pin "21") (pinfunction "A0_21") (pintype "input"))
      (node (ref "IC6") (pin "3") (pinfunction "A2_3") (pintype "input"))
      (node (ref "IC7") (pin "4") (pinfunction "GND_4") (pintype "power_in"))
      (node (ref "IC8") (pin "15") (pinfunction "OSC_15") (pintype "input"))
      (node (ref "IC8") (pin "16") (pinfunction "A0_16") (pintype "input"))
      (node (ref "IC8") (pin "17") (pinfunction "A1_17") (pintype "input"))
      (node (ref "IC8") (pin "18") (pinfunction "A2_18") (pintype "input"))
      (node (ref "IC8") (pin "19") (pinfunction "SA0_19") (pintype "input"))
      (node (ref "IC8") (pin "20") (pinfunction "VSS_20") (pintype "power_in"))
      (node (ref "LOCH1") (pin "B3,0") (pinfunction "MOUNT_B3,0") (pintype "passive"))
      (node (ref "LOCH2") (pin "B3,0") (pinfunction "MOUNT_B3,0") (pintype "passive"))
      (node (ref "R10") (pin "1") (pinfunction "1_1") (pintype "passive"))
      (node (ref "R20") (pin "1") (pinfunction "1_1") (pintype "passive"))
      (node (ref "R23") (pin "1") (pinfunction "1_1") (pintype "passive"))
      (node (ref "R24") (pin "3") (pinfunction "A_3") (pintype "passive"))
      (node (ref "R29") (pin "1") (pinfunction "1_1") (pintype "passive"))
      (node (ref "R3") (pin "1") (pinfunction "1_1") (pintype "passive"))
      (node (ref "R30") (pin "1") (pinfunction "1_1") (pintype "passive"))
      (node (ref "R31") (pin "2") (pinfunction "2_2") (pintype "passive"))
      (node (ref "R6") (pin "2") (pinfunction "2_2") (pintype "passive"))
      (node (ref "RF-POWER") (pin "1") (pinfunction "E_1") (pintype "passive"))
      (node (ref "RF-POWER") (pin "4") (pinfunction "P$1_4") (pintype "power_in"))
      (node (ref "RF-POWER") (pin "5") (pinfunction "P$2_5") (pintype "power_in"))
      (node (ref "SQUELCH") (pin "1") (pinfunction "E_1") (pintype "passive"))
      (node (ref "SQUELCH") (pin "4") (pinfunction "P$1_4") (pintype "power_in"))
      (node (ref "SQUELCH") (pin "5") (pinfunction "P$2_5") (pintype "power_in"))
      (node (ref "SW01") (pin "1") (pinfunction "1_1") (pintype "passive"))
      (node (ref "SW01") (pin "2") (pinfunction "2_2") (pintype "passive"))
      (node (ref "SW02") (pin "1") (pinfunction "1_1") (pintype "passive"))
      (node (ref "SW02") (pin "2") (pinfunction "2_2") (pintype "passive"))
      (node (ref "SW03") (pin "1") (pinfunction "1_1") (pintype "passive"))
      (node (ref "SW03") (pin "2") (pinfunction "2_2") (pintype "passive"))
      (node (ref "SW04") (pin "1") (pinfunction "1_1") (pintype "passive"))
      (node (ref "SW04") (pin "2") (pinfunction "2_2") (pintype "passive"))
      (node (ref "SW05") (pin "1") (pinfunction "1_1") (pintype "passive"))
      (node (ref "SW05") (pin "2") (pinfunction "2_2") (pintype "passive"))
      (node (ref "SW06") (pin "1") (pinfunction "1_1") (pintype "passive"))
      (node (ref "SW06") (pin "2") (pinfunction "2_2") (pintype "passive"))
      (node (ref "SW07") (pin "1") (pinfunction "1_1") (pintype "passive"))
      (node (ref "SW07") (pin "2") (pinfunction "2_2") (pintype "passive"))
      (node (ref "SW08") (pin "1") (pinfunction "1_1") (pintype "passive"))
      (node (ref "SW08") (pin "2") (pinfunction "2_2") (pintype "passive"))
      (node (ref "SW09") (pin "1") (pinfunction "1_1") (pintype "passive"))
      (node (ref "SW09") (pin "2") (pinfunction "2_2") (pintype "passive"))
      (node (ref "SW10") (pin "1") (pinfunction "1_1") (pintype "passive"))
      (node (ref "SW10") (pin "2") (pinfunction "2_2") (pintype "passive"))
      (node (ref "SW11") (pin "1") (pinfunction "1_1") (pintype "passive"))
      (node (ref "SW11") (pin "2") (pinfunction "2_2") (pintype "passive"))
      (node (ref "SW12") (pin "1") (pinfunction "1_1") (pintype "passive"))
      (node (ref "SW12") (pin "2") (pinfunction "2_2") (pintype "passive"))
      (node (ref "SW13") (pin "1") (pinfunction "1_1") (pintype "passive"))
      (node (ref "SW13") (pin "2") (pinfunction "2_2") (pintype "passive"))
      (node (ref "SW14") (pin "1") (pinfunction "1_1") (pintype "passive"))
      (node (ref "SW14") (pin "2") (pinfunction "2_2") (pintype "passive"))
      (node (ref "SW15") (pin "1") (pinfunction "1_1") (pintype "passive"))
      (node (ref "SW15") (pin "2") (pinfunction "2_2") (pintype "passive"))
      (node (ref "SW16") (pin "1") (pinfunction "1_1") (pintype "passive"))
      (node (ref "SW16") (pin "2") (pinfunction "2_2") (pintype "passive"))
      (node (ref "SW17") (pin "1") (pinfunction "1_1") (pintype "passive"))
      (node (ref "SW17") (pin "2") (pinfunction "2_2") (pintype "passive"))
      (node (ref "SW18") (pin "1") (pinfunction "1_1") (pintype "passive"))
      (node (ref "SW18") (pin "2") (pinfunction "2_2") (pintype "passive"))
      (node (ref "SW19") (pin "1") (pinfunction "1_1") (pintype "passive"))
      (node (ref "SW19") (pin "2") (pinfunction "2_2") (pintype "passive"))
      (node (ref "SW20") (pin "1") (pinfunction "1_1") (pintype "passive"))
      (node (ref "SW20") (pin "2") (pinfunction "2_2") (pintype "passive"))
      (node (ref "SW21") (pin "1") (pinfunction "1_1") (pintype "passive"))
      (node (ref "SW21") (pin "2") (pinfunction "2_2") (pintype "passive"))
      (node (ref "SW22") (pin "C") (pinfunction "C_C") (pintype "passive"))
      (node (ref "SW22") (pin "GND@1") (pinfunction "GND_GND@1") (pintype "power_in"))
      (node (ref "SW22") (pin "GND@2") (pinfunction "GND_GND@2") (pintype "power_in"))
      (node (ref "SW22") (pin "GND@3") (pinfunction "GND_GND@3") (pintype "power_in"))
      (node (ref "SW22") (pin "GND@4") (pinfunction "GND_GND@4") (pintype "power_in"))
      (node (ref "SW22") (pin "GND@5") (pinfunction "GND_GND@5") (pintype "power_in"))
      (node (ref "SW22") (pin "GND@6") (pinfunction "GND_GND@6") (pintype "power_in"))
      (node (ref "SW22") (pin "GND@7") (pinfunction "GND_GND@7") (pintype "power_in"))
      (node (ref "SW22") (pin "GND@8") (pinfunction "GND_GND@8") (pintype "power_in"))
      (node (ref "SWR/CAL") (pin "1") (pinfunction "E_1") (pintype "passive"))
      (node (ref "SWR/CAL") (pin "4") (pinfunction "P$1_4") (pintype "power_in"))
      (node (ref "SWR/CAL") (pin "5") (pinfunction "P$2_5") (pintype "power_in"))
      (node (ref "T1") (pin "3") (pinfunction "E_3") (pintype "passive"))
      (node (ref "T4") (pin "3") (pinfunction "E_3") (pintype "passive"))
      (node (ref "T5") (pin "C") (pinfunction "C_C") (pintype "passive"))
      (node (ref "T6") (pin "C") (pinfunction "C_C") (pintype "passive"))
      (node (ref "U1") (pin "2") (pinfunction "2_2") (pintype "passive"))
      (node (ref "U2") (pin "9") (pinfunction "9_9") (pintype "passive"))
      (node (ref "VOLUME") (pin "4") (pinfunction "P$1_4") (pintype "power_in"))
      (node (ref "VOLUME") (pin "5") (pinfunction "P$2_5") (pintype "power_in"))
    )
    (net (code "4") (name "Net-(C1-Pad1)") (class "Default")
      (node (ref "C1") (pin "1") (pinfunction "1_1") (pintype "passive"))
      (node (ref "C2") (pin "2") (pinfunction "2_2") (pintype "passive"))
      (node (ref "R28") (pin "2") (pinfunction "2_2") (pintype "passive"))
    )
    (net (code "5") (name "Net-(C1-Pad2)") (class "Default")
      (node (ref "C1") (pin "2") (pinfunction "2_2") (pintype "passive"))
      (node (ref "U1") (pin "5") (pinfunction "5_5") (pintype "passive"))
    )
    (net (code "6") (name "Net-(C4-Pad-)") (class "Default")
      (node (ref "C4") (pin "-") (pinfunction "-_-") (pintype "passive"))
      (node (ref "R15") (pin "2") (pinfunction "2_2") (pintype "passive"))
      (node (ref "R31") (pin "1") (pinfunction "1_1") (pintype "passive"))
    )
    (net (code "7") (name "Net-(C18-Pad1)") (class "Default")
      (node (ref "C18") (pin "1") (pinfunction "1_1") (pintype "passive"))
      (node (ref "PTT") (pin "MP") (pinfunction "MP_MP") (pintype "passive"))
      (node (ref "R8") (pin "2") (pinfunction "2_2") (pintype "passive"))
    )
    (net (code "8") (name "Net-(C25-Pad2)") (class "Default")
      (node (ref "C25") (pin "2") (pinfunction "2_2") (pintype "passive"))
      (node (ref "D1") (pin "A") (pinfunction "A_A") (pintype "passive"))
      (node (ref "D2") (pin "A") (pinfunction "A_A") (pintype "passive"))
      (node (ref "D3") (pin "A") (pinfunction "A_A") (pintype "passive"))
      (node (ref "U1") (pin "1") (pinfunction "1_1") (pintype "passive"))
    )
    (net (code "9") (name "Net-(C32-Pad2)") (class "Default")
      (node (ref "C32") (pin "2") (pinfunction "2_2") (pintype "passive"))
      (node (ref "R2") (pin "2") (pinfunction "2_2") (pintype "passive"))
      (node (ref "R4") (pin "2") (pinfunction "2_2") (pintype "passive"))
      (node (ref "U2") (pin "5") (pinfunction "5_5") (pintype "passive"))
    )
    (net (code "10") (name "Net-(CLARIFIER-A)") (class "Default")
      (node (ref "CLARIFIER") (pin "3") (pinfunction "A_3") (pintype "passive"))
      (node (ref "R6") (pin "1") (pinfunction "1_1") (pintype "passive"))
    )
    (net (code "11") (name "Net-(CLARIFIER-E)") (class "Default")
      (node (ref "CLARIFIER") (pin "1") (pinfunction "E_1") (pintype "passive"))
      (node (ref "R5") (pin "1") (pinfunction "1_1") (pintype "passive"))
    )
    (net (code "12") (name "Net-(CLARIFIER-S)") (class "Default")
      (node (ref "CLARIFIER") (pin "2") (pinfunction "S_2") (pintype "passive"))
      (node (ref "U2") (pin "7") (pinfunction "7_7") (pintype "passive"))
    )
    (net (code "13") (name "Net-(D4-PadC)") (class "Default")
      (node (ref "D4") (pin "C") (pinfunction "C_C") (pintype "passive"))
      (node (ref "R4") (pin "1") (pinfunction "1_1") (pintype "passive"))
      (node (ref "R5") (pin "2") (pinfunction "2_2") (pintype "passive"))
    )
    (net (code "14") (name "Net-(DISPLAY1-D1_A)") (class "Default")
      (node (ref "DISPLAY1") (pin "A1") (pinfunction "D1_A_A1") (pintype "input"))
      (node (ref "DISPLAY1") (pin "A3") (pinfunction "D3_A_A3") (pintype "input"))
      (node (ref "LED02") (pin "A") (pinfunction "A_A") (pintype "passive"))
      (node (ref "LED04") (pin "A") (pinfunction "A_A") (pintype "passive"))
      (node (ref "LED06") (pin "A") (pinfunction "A_A") (pintype "passive"))
      (node (ref "LED08") (pin "A") (pinfunction "A_A") (pintype "passive"))
      (node (ref "LED10") (pin "A") (pinfunction "A_A") (pintype "passive"))
      (node (ref "LED12") (pin "A") (pinfunction "A_A") (pintype "passive"))
      (node (ref "LED14") (pin "A") (pinfunction "A_A") (pintype "passive"))
      (node (ref "LED16") (pin "A") (pinfunction "A_A") (pintype "passive"))
      (node (ref "LED18") (pin "A") (pinfunction "A_A") (pintype "passive"))
      (node (ref "LED20") (pin "A") (pinfunction "A_A") (pintype "passive"))
      (node (ref "T3") (pin "3") (pinfunction "E_3") (pintype "passive"))
    )
    (net (code "15") (name "Net-(DISPLAY1-D1_K)") (class "Default")
      (node (ref "DISPLAY1") (pin "K1") (pinfunction "D1_K_K1") (pintype "input"))
      (node (ref "DISPLAY1") (pin "K3") (pinfunction "D3_K_K3") (pintype "input"))
      (node (ref "IC3") (pin "17") (pinfunction "/OUT10_17") (pintype "bidirectional"))
    )
    (net (code "16") (name "Net-(DISPLAY1-D2_A)") (class "Default")
      (node (ref "DISPLAY1") (pin "A2") (pinfunction "D2_A_A2") (pintype "input"))
      (node (ref "DISPLAY1") (pin "A4") (pinfunction "D4_A_A4") (pintype "input"))
      (node (ref "LED01") (pin "A") (pinfunction "A_A") (pintype "passive"))
      (node (ref "LED03") (pin "A") (pinfunction "A_A") (pintype "passive"))
      (node (ref "LED05") (pin "A") (pinfunction "A_A") (pintype "passive"))
      (node (ref "LED07") (pin "A") (pinfunction "A_A") (pintype "passive"))
      (node (ref "LED09") (pin "A") (pinfunction "A_A") (pintype "passive"))
      (node (ref "LED11") (pin "A") (pinfunction "A_A") (pintype "passive"))
      (node (ref "LED13") (pin "A") (pinfunction "A_A") (pintype "passive"))
      (node (ref "LED15") (pin "A") (pinfunction "A_A") (pintype "passive"))
      (node (ref "LED17") (pin "A") (pinfunction "A_A") (pintype "passive"))
      (node (ref "LED19") (pin "A") (pinfunction "A_A") (pintype "passive"))
      (node (ref "T2") (pin "3") (pinfunction "E_3") (pintype "passive"))
    )
    (net (code "17") (name "Net-(DISPLAY1-D2_K)") (class "Default")
      (node (ref "DISPLAY1") (pin "K2") (pinfunction "D2_K_K2") (pintype "input"))
      (node (ref "DISPLAY1") (pin "K4") (pinfunction "D4_K_K4") (pintype "input"))
      (node (ref "IC3") (pin "18") (pinfunction "/OUT11_18") (pintype "bidirectional"))
    )
    (net (code "18") (name "Net-(IC1-(A8)PC0)") (class "Default")
      (node (ref "IC1") (pin "35") (pinfunction "(A8)PC0_35") (pintype "output"))
      (node (ref "R14") (pin "2") (pinfunction "2_2") (pintype "passive"))
    )
    (net (code "19") (name "Net-(IC1-(A9)PC1)") (class "Default")
      (node (ref "IC1") (pin "36") (pinfunction "(A9)PC1_36") (pintype "output"))
      (node (ref "R16") (pin "2") (pinfunction "2_2") (pintype "passive"))
    )
    (net (code "20") (name "Net-(IC1-(A11)PC3)") (class "Default")
      (node (ref "C29") (pin "2") (pinfunction "2_2") (pintype "passive"))
      (node (ref "IC1") (pin "38") (pinfunction "(A11)PC3_38") (pintype "output"))
      (node (ref "PC3") (pin "MP") (pinfunction "MP_MP") (pintype "passive"))
    )
    (net (code "21") (name "Net-(IC1-(A12)PC4)") (class "Default")
      (node (ref "C28") (pin "2") (pinfunction "2_2") (pintype "passive"))
      (node (ref "IC1") (pin "39") (pinfunction "(A12)PC4_39") (pintype "output"))
      (node (ref "PC4") (pin "MP") (pinfunction "MP_MP") (pintype "passive"))
    )
    (net (code "22") (name "Net-(IC1-(A13)PC5)") (class "Default")
      (node (ref "C27") (pin "2") (pinfunction "2_2") (pintype "passive"))
      (node (ref "IC1") (pin "40") (pinfunction "(A13)PC5_40") (pintype "output"))
      (node (ref "PC5") (pin "MP") (pinfunction "MP_MP") (pintype "passive"))
    )
    (net (code "23") (name "Net-(IC1-(AD2)PA2)") (class "Default")
      (node (ref "C26") (pin "2") (pinfunction "2_2") (pintype "passive"))
      (node (ref "IC1") (pin "49") (pinfunction "(AD2)PA2_49") (pintype "bidirectional"))
      (node (ref "R29") (pin "2") (pinfunction "2_2") (pintype "passive"))
      (node (ref "U1") (pin "6") (pinfunction "6_6") (pintype "passive"))
    )
    (net (code "24") (name "Net-(IC1-(AD3)PA3)") (class "Default")
      (node (ref "C11") (pin "2") (pinfunction "2_2") (pintype "passive"))
      (node (ref "IC1") (pin "48") (pinfunction "(AD3)PA3_48") (pintype "bidirectional"))
      (node (ref "U1") (pin "8") (pinfunction "8_8") (pintype "passive"))
    )
    (net (code "25") (name "Net-(IC1-(AD4)PA4)") (class "Default")
      (node (ref "C12") (pin "2") (pinfunction "2_2") (pintype "passive"))
      (node (ref "IC1") (pin "47") (pinfunction "(AD4)PA4_47") (pintype "bidirectional"))
      (node (ref "U1") (pin "10") (pinfunction "10_10") (pintype "passive"))
    )
    (net (code "26") (name "Net-(IC1-(AD5)PA5)") (class "Default")
      (node (ref "C10") (pin "2") (pinfunction "2_2") (pintype "passive"))
      (node (ref "IC1") (pin "46") (pinfunction "(AD5)PA5_46") (pintype "bidirectional"))
      (node (ref "U1") (pin "9") (pinfunction "9_9") (pintype "passive"))
    )
    (net (code "27") (name "Net-(IC1-(AD6)PA6)") (class "Default")
      (node (ref "C9") (pin "2") (pinfunction "2_2") (pintype "passive"))
      (node (ref "IC1") (pin "45") (pinfunction "(AD6)PA6_45") (pintype "bidirectional"))
      (node (ref "U1") (pin "7") (pinfunction "7_7") (pintype "passive"))
    )
    (net (code "28") (name "Net-(IC1-(AD7)PA7)") (class "Default")
      (node (ref "IC1") (pin "44") (pinfunction "(AD7)PA7_44") (pintype "bidirectional"))
      (node (ref "R12") (pin "1") (pinfunction "1_1") (pintype "passive"))
    )
    (net (code "29") (name "Net-(IC1-(IC3{slash}INT7)PE7)") (class "Default")
      (node (ref "C3") (pin "+") (pinfunction "+_+") (pintype "passive"))
      (node (ref "IC1") (pin "9") (pinfunction "(IC3/INT7)PE7_9") (pintype "bidirectional"))
      (node (ref "R25") (pin "1") (pinfunction "1_1") (pintype "passive"))
    )
    (net (code "30") (name "Net-(IC1-(MISO)PB3)") (class "Default")
      (node (ref "IC1") (pin "13") (pinfunction "(MISO)PB3_13") (pintype "bidirectional"))
      (node (ref "IC7") (pin "2") (pinfunction "SO_2") (pintype "bidirectional"))
    )
    (net (code "31") (name "Net-(IC1-(MOSI)PB2)") (class "Default")
      (node (ref "IC1") (pin "12") (pinfunction "(MOSI)PB2_12") (pintype "bidirectional"))
      (node (ref "IC7") (pin "5") (pinfunction "SI_5") (pintype "input"))
    )
    (net (code "32") (name "Net-(IC1-(OC1A)PB5)") (class "Default")
      (node (ref "IC1") (pin "15") (pinfunction "(OC1A)PB5_15") (pintype "bidirectional"))
      (node (ref "R24") (pin "1") (pinfunction "E_1") (pintype "passive"))
    )
    (net (code "33") (name "Net-(IC1-(OC3A{slash}AIN1)PE3)") (class "Default")
      (node (ref "IC1") (pin "5") (pinfunction "(OC3A/AIN1)PE3_5") (pintype "bidirectional"))
      (node (ref "SPK") (pin "MP") (pinfunction "MP_MP") (pintype "passive"))
    )
    (net (code "34") (name "Net-(IC1-(OC3B{slash}INT4)PE4)") (class "Default")
      (node (ref "C31") (pin "1") (pinfunction "1_1") (pintype "passive"))
      (node (ref "D3") (pin "C") (pinfunction "C_C") (pintype "passive"))
      (node (ref "IC1") (pin "6") (pinfunction "(OC3B/INT4)PE4_6") (pintype "bidirectional"))
      (node (ref "R23") (pin "2") (pinfunction "2_2") (pintype "passive"))
    )
    (net (code "35") (name "Net-(IC1-(OC3C{slash}INT5)PE5)") (class "Default")
      (node (ref "IC1") (pin "7") (pinfunction "(OC3C/INT5)PE5_7") (pintype "bidirectional"))
      (node (ref "SW01") (pin "3") (pinfunction "3_3") (pintype "passive"))
      (node (ref "SW01") (pin "4") (pinfunction "4_4") (pintype "passive"))
    )
    (net (code "36") (name "Net-(IC1-(RXD1{slash}INT2)PD2)") (class "Default")
      (node (ref "IC1") (pin "27") (pinfunction "(RXD1/INT2)PD2_27") (pintype "bidirectional"))
      (node (ref "RX") (pin "MP") (pinfunction "MP_MP") (pintype "passive"))
    )
    (net (code "37") (name "Net-(IC1-(RXD{slash}PDI)PE0)") (class "Default")
      (node (ref "IC1") (pin "2") (pinfunction "(RXD/PDI)PE0_2") (pintype "bidirectional"))
      (node (ref "PDI") (pin "MP") (pinfunction "MP_MP") (pintype "passive"))
    )
    (net (code "38") (name "Net-(IC1-(SCK)PB1)") (class "Default")
      (node (ref "IC1") (pin "11") (pinfunction "(SCK)PB1_11") (pintype "bidirectional"))
      (node (ref "IC7") (pin "6") (pinfunction "SCK_6") (pintype "input"))
      (node (ref "SCK") (pin "MP") (pinfunction "MP_MP") (pintype "passive"))
    )
    (net (code "39") (name "Net-(IC1-(SS)PB0)") (class "Default")
      (node (ref "IC1") (pin "10") (pinfunction "(SS)PB0_10") (pintype "bidirectional"))
      (node (ref "IC7") (pin "1") (pinfunction "~{CS}_1") (pintype "input"))
    )
    (net (code "40") (name "Net-(IC1-(T3{slash}INT6)PE6)") (class "Default")
      (node (ref "C30") (pin "1") (pinfunction "1_1") (pintype "passive"))
      (node (ref "IC1") (pin "8") (pinfunction "(T3/INT6)PE6_8") (pintype "bidirectional"))
      (node (ref "PE6") (pin "MP") (pinfunction "MP_MP") (pintype "passive"))
    )
    (net (code "41") (name "Net-(IC1-(TXD1{slash}INT3)PD3)") (class "Default")
      (node (ref "IC1") (pin "28") (pinfunction "(TXD1/INT3)PD3_28") (pintype "bidirectional"))
      (node (ref "TX") (pin "MP") (pinfunction "MP_MP") (pintype "passive"))
    )
    (net (code "42") (name "Net-(IC1-(TXD{slash}PDO)PE1)") (class "Default")
      (node (ref "IC1") (pin "3") (pinfunction "(TXD/PDO)PE1_3") (pintype "bidirectional"))
      (node (ref "PDO") (pin "MP") (pinfunction "MP_MP") (pintype "passive"))
    )
    (net (code "43") (name "Net-(IC1-AVCC)") (class "Default")
      (node (ref "C7") (pin "2") (pinfunction "2_2") (pintype "passive"))
      (node (ref "IC1") (pin "64") (pinfunction "AVCC_64") (pintype "power_in"))
      (node (ref "L1") (pin "1") (pinfunction "1_1") (pintype "passive"))
    )
    (net (code "44") (name "Net-(IC1-PF1(ADC1))") (class "Default")
      (node (ref "IC1") (pin "60") (pinfunction "PF1(ADC1)_60") (pintype "input"))
      (node (ref "SWR/CAL") (pin "3") (pinfunction "A_3") (pintype "passive"))
      (node (ref "U2") (pin "10") (pinfunction "10_10") (pintype "passive"))
    )
    (net (code "45") (name "Net-(IC1-RESET)") (class "Default")
      (node (ref "IC1") (pin "20") (pinfunction "RESET_20") (pintype "input"))
      (node (ref "R32") (pin "1") (pinfunction "1_1") (pintype "passive"))
      (node (ref "RST") (pin "MP") (pinfunction "MP_MP") (pintype "passive"))
    )
    (net (code "46") (name "Net-(IC1-XTAL1)") (class "Default")
      (node (ref "C6") (pin "2") (pinfunction "2_2") (pintype "passive"))
      (node (ref "IC1") (pin "24") (pinfunction "XTAL1_24") (pintype "bidirectional"))
      (node (ref "Q1") (pin "2") (pinfunction "2_2") (pintype "passive"))
    )
    (net (code "47") (name "Net-(IC1-XTAL2)") (class "Default")
      (node (ref "C5") (pin "2") (pinfunction "2_2") (pintype "passive"))
      (node (ref "IC1") (pin "23") (pinfunction "XTAL2_23") (pintype "bidirectional"))
      (node (ref "Q1") (pin "1") (pinfunction "1_1") (pintype "passive"))
    )
    (net (code "48") (name "Net-(IC2A-+IN)") (class "Default")
      (node (ref "C20") (pin "2") (pinfunction "2_2") (pintype "passive"))
      (node (ref "IC2") (pin "3") (pinfunction "+IN_3") (pintype "input"))
      (node (ref "IC2") (pin "6") (pinfunction "-IN_6") (pintype "input"))
      (node (ref "R10") (pin "2") (pinfunction "2_2") (pintype "passive"))
      (node (ref "R17") (pin "1") (pinfunction "1_1") (pintype "passive"))
      (node (ref "UP/DOWN") (pin "MP") (pinfunction "MP_MP") (pintype "passive"))
    )
    (net (code "49") (name "Net-(IC2A--IN)") (class "Default")
      (node (ref "IC2") (pin "2") (pinfunction "-IN_2") (pintype "input"))
      (node (ref "R18") (pin "1") (pinfunction "1_1") (pintype "passive"))
      (node (ref "R19") (pin "2") (pinfunction "2_2") (pintype "passive"))
    )
    (net (code "50") (name "Net-(IC2A-OUT)") (class "Default")
      (node (ref "IC2") (pin "1") (pinfunction "OUT_1") (pintype "output"))
      (node (ref "R11") (pin "2") (pinfunction "2_2") (pintype "passive"))
      (node (ref "R21") (pin "2") (pinfunction "2_2") (pintype "passive"))
    )
    (net (code "51") (name "Net-(IC2B-+IN)") (class "Default")
      (node (ref "IC2") (pin "5") (pinfunction "+IN_5") (pintype "input"))
      (node (ref "R19") (pin "1") (pinfunction "1_1") (pintype "passive"))
      (node (ref "R20") (pin "2") (pinfunction "2_2") (pintype "passive"))
    )
    (net (code "52") (name "Net-(IC2B-OUT)") (class "Default")
      (node (ref "IC2") (pin "7") (pinfunction "OUT_7") (pintype "output"))
      (node (ref "R1") (pin "2") (pinfunction "2_2") (pintype "passive"))
      (node (ref "R22") (pin "2") (pinfunction "2_2") (pintype "passive"))
    )
    (net (code "53") (name "Net-(IC2C-V+)") (class "Default")
      (node (ref "C14") (pin "2") (pinfunction "2_2") (pintype "passive"))
      (node (ref "C19") (pin "2") (pinfunction "2_2") (pintype "passive"))
      (node (ref "IC2") (pin "8") (pinfunction "V+_8") (pintype "power_in"))
      (node (ref "IC4") (pin "1") (pinfunction "VI_1") (pintype "input"))
      (node (ref "R17") (pin "2") (pinfunction "2_2") (pintype "passive"))
      (node (ref "R18") (pin "2") (pinfunction "2_2") (pintype "passive"))
      (node (ref "U1") (pin "4") (pinfunction "4_4") (pintype "passive"))
    )
    (net (code "54") (name "Net-(IC3-REXT)") (class "Default")
      (node (ref "IC3") (pin "1") (pinfunction "REXT_1") (pintype "bidirectional"))
      (node (ref "R3") (pin "2") (pinfunction "2_2") (pintype "passive"))
    )
    (net (code "55") (name "Net-(IC3-{slash}OUT0)") (class "Default")
      (node (ref "IC3") (pin "6") (pinfunction "/OUT0_6") (pintype "bidirectional"))
      (node (ref "LED05") (pin "C") (pinfunction "C_C") (pintype "passive"))
      (node (ref "LED06") (pin "C") (pinfunction "C_C") (pintype "passive"))
    )
    (net (code "56") (name "Net-(IC3-{slash}OUT1)") (class "Default")
      (node (ref "IC3") (pin "7") (pinfunction "/OUT1_7") (pintype "bidirectional"))
      (node (ref "LED07") (pin "C") (pinfunction "C_C") (pintype "passive"))
      (node (ref "LED08") (pin "C") (pinfunction "C_C") (pintype "passive"))
    )
    (net (code "57") (name "Net-(IC3-{slash}OUT2)") (class "Default")
      (node (ref "IC3") (pin "8") (pinfunction "/OUT2_8") (pintype "bidirectional"))
      (node (ref "LED09") (pin "C") (pinfunction "C_C") (pintype "passive"))
      (node (ref "LED10") (pin "C") (pinfunction "C_C") (pintype "passive"))
    )
    (net (code "58") (name "Net-(IC3-{slash}OUT3)") (class "Default")
      (node (ref "IC3") (pin "9") (pinfunction "/OUT3_9") (pintype "bidirectional"))
      (node (ref "LED11") (pin "C") (pinfunction "C_C") (pintype "passive"))
      (node (ref "LED12") (pin "C") (pinfunction "C_C") (pintype "passive"))
    )
    (net (code "59") (name "Net-(IC3-{slash}OUT4)") (class "Default")
      (node (ref "IC3") (pin "11") (pinfunction "/OUT4_11") (pintype "bidirectional"))
      (node (ref "LED13") (pin "C") (pinfunction "C_C") (pintype "passive"))
      (node (ref "LED14") (pin "C") (pinfunction "C_C") (pintype "passive"))
    )
    (net (code "60") (name "Net-(IC3-{slash}OUT5)") (class "Default")
      (node (ref "IC3") (pin "12") (pinfunction "/OUT5_12") (pintype "bidirectional"))
      (node (ref "LED15") (pin "C") (pinfunction "C_C") (pintype "passive"))
      (node (ref "LED16") (pin "C") (pinfunction "C_C") (pintype "passive"))
    )
    (net (code "61") (name "Net-(IC3-{slash}OUT6)") (class "Default")
      (node (ref "IC3") (pin "13") (pinfunction "/OUT6_13") (pintype "bidirectional"))
      (node (ref "LED19") (pin "C") (pinfunction "C_C") (pintype "passive"))
      (node (ref "LED20") (pin "C") (pinfunction "C_C") (pintype "passive"))
    )
    (net (code "62") (name "Net-(IC3-{slash}OUT7)") (class "Default")
      (node (ref "IC3") (pin "14") (pinfunction "/OUT7_14") (pintype "bidirectional"))
      (node (ref "LED17") (pin "C") (pinfunction "C_C") (pintype "passive"))
      (node (ref "LED18") (pin "C") (pinfunction "C_C") (pintype "passive"))
    )
    (net (code "63") (name "Net-(IC3-{slash}OUT8)") (class "Default")
      (node (ref "IC3") (pin "15") (pinfunction "/OUT8_15") (pintype "bidirectional"))
      (node (ref "LED03") (pin "C") (pinfunction "C_C") (pintype "passive"))
      (node (ref "LED04") (pin "C") (pinfunction "C_C") (pintype "passive"))
    )
    (net (code "64") (name "Net-(IC3-{slash}OUT9)") (class "Default")
      (node (ref "IC3") (pin "16") (pinfunction "/OUT9_16") (pintype "bidirectional"))
      (node (ref "LED01") (pin "C") (pinfunction "C_C") (pintype "passive"))
      (node (ref "LED02") (pin "C") (pinfunction "C_C") (pintype "passive"))
    )
    (net (code "65") (name "Net-(IC3-{slash}RESET)") (class "Default")
      (node (ref "IC3") (pin "25") (pinfunction "/RESET_25") (pintype "bidirectional"))
      (node (ref "R13") (pin "2") (pinfunction "2_2") (pintype "passive"))
    )
    (net (code "66") (name "Net-(IC4-VO)") (class "Default")
      (node (ref "C15") (pin "2") (pinfunction "2_2") (pintype "passive"))
      (node (ref "IC4") (pin "2") (pinfunction "VO_2") (pintype "passive"))
      (node (ref "T2") (pin "4") (pinfunction "C_4") (pintype "passive"))
      (node (ref "T3") (pin "4") (pinfunction "C_4") (pintype "passive"))
    )
    (net (code "67") (name "Net-(IC5-I{slash}O0.0)") (class "Default")
      (node (ref "IC5") (pin "4") (pinfunction "I/O0.0_4") (pintype "bidirectional"))
      (node (ref "SW13") (pin "3") (pinfunction "3_3") (pintype "passive"))
      (node (ref "SW13") (pin "4") (pinfunction "4_4") (pintype "passive"))
    )
    (net (code "68") (name "Net-(IC5-I{slash}O0.1)") (class "Default")
      (node (ref "IC5") (pin "5") (pinfunction "I/O0.1_5") (pintype "bidirectional"))
      (node (ref "SW14") (pin "3") (pinfunction "3_3") (pintype "passive"))
      (node (ref "SW14") (pin "4") (pinfunction "4_4") (pintype "passive"))
    )
    (net (code "69") (name "Net-(IC5-I{slash}O0.2)") (class "Default")
      (node (ref "IC5") (pin "6") (pinfunction "I/O0.2_6") (pintype "bidirectional"))
      (node (ref "SW15") (pin "3") (pinfunction "3_3") (pintype "passive"))
      (node (ref "SW15") (pin "4") (pinfunction "4_4") (pintype "passive"))
    )
    (net (code "70") (name "Net-(IC5-I{slash}O0.6)") (class "Default")
      (node (ref "IC5") (pin "10") (pinfunction "I/O0.6_10") (pintype "bidirectional"))
      (node (ref "T5") (pin "E") (pinfunction "E_E") (pintype "passive"))
    )
    (net (code "71") (name "Net-(IC5-I{slash}O0.7)") (class "Default")
      (node (ref "IC5") (pin "11") (pinfunction "I/O0.7_11") (pintype "bidirectional"))
      (node (ref "T6") (pin "E") (pinfunction "E_E") (pintype "passive"))
    )
    (net (code "72") (name "Net-(IC5-I{slash}O1.0)") (class "Default")
      (node (ref "IC5") (pin "13") (pinfunction "I/O1.0_13") (pintype "bidirectional"))
      (node (ref "SW20") (pin "3") (pinfunction "3_3") (pintype "passive"))
      (node (ref "SW20") (pin "4") (pinfunction "4_4") (pintype "passive"))
    )
    (net (code "73") (name "Net-(IC5-I{slash}O1.1)") (class "Default")
      (node (ref "C21") (pin "2") (pinfunction "2_2") (pintype "passive"))
      (node (ref "IC5") (pin "14") (pinfunction "I/O1.1_14") (pintype "bidirectional"))
      (node (ref "SW22") (pin "B") (pinfunction "B_B") (pintype "passive"))
    )
    (net (code "74") (name "Net-(IC5-I{slash}O1.2)") (class "Default")
      (node (ref "C22") (pin "2") (pinfunction "2_2") (pintype "passive"))
      (node (ref "IC5") (pin "15") (pinfunction "I/O1.2_15") (pintype "bidirectional"))
      (node (ref "SW22") (pin "A") (pinfunction "A_A") (pintype "passive"))
    )
    (net (code "75") (name "Net-(IC5-I{slash}O1.3)") (class "Default")
      (node (ref "IC5") (pin "16") (pinfunction "I/O1.3_16") (pintype "bidirectional"))
      (node (ref "SW21") (pin "3") (pinfunction "3_3") (pintype "passive"))
      (node (ref "SW21") (pin "4") (pinfunction "4_4") (pintype "passive"))
    )
    (net (code "76") (name "Net-(IC5-I{slash}O1.4)") (class "Default")
      (node (ref "IC5") (pin "17") (pinfunction "I/O1.4_17") (pintype "bidirectional"))
      (node (ref "SW18") (pin "3") (pinfunction "3_3") (pintype "passive"))
      (node (ref "SW18") (pin "4") (pinfunction "4_4") (pintype "passive"))
    )
    (net (code "77") (name "Net-(IC5-I{slash}O1.5)") (class "Default")
      (node (ref "IC5") (pin "18") (pinfunction "I/O1.5_18") (pintype "bidirectional"))
      (node (ref "SW19") (pin "3") (pinfunction "3_3") (pintype "passive"))
      (node (ref "SW19") (pin "4") (pinfunction "4_4") (pintype "passive"))
    )
    (net (code "78") (name "Net-(IC5-I{slash}O1.6)") (class "Default")
      (node (ref "IC5") (pin "19") (pinfunction "I/O1.6_19") (pintype "bidirectional"))
      (node (ref "SW16") (pin "3") (pinfunction "3_3") (pintype "passive"))
      (node (ref "SW16") (pin "4") (pinfunction "4_4") (pintype "passive"))
    )
    (net (code "79") (name "Net-(IC5-I{slash}O1.7)") (class "Default")
      (node (ref "IC5") (pin "20") (pinfunction "I/O1.7_20") (pintype "bidirectional"))
      (node (ref "SW17") (pin "3") (pinfunction "3_3") (pintype "passive"))
      (node (ref "SW17") (pin "4") (pinfunction "4_4") (pintype "passive"))
    )
    (net (code "80") (name "Net-(IC5-~{INT})") (class "Default")
      (node (ref "IC5") (pin "1") (pinfunction "~{INT}_1") (pintype "output"))
      (node (ref "IC6") (pin "1") (pinfunction "~{INT}_1") (pintype "output"))
      (node (ref "R25") (pin "2") (pinfunction "2_2") (pintype "passive"))
    )
    (net (code "81") (name "Net-(IC6-I{slash}O0.0)") (class "Default")
      (node (ref "IC6") (pin "4") (pinfunction "I/O0.0_4") (pintype "bidirectional"))
      (node (ref "SW08") (pin "3") (pinfunction "3_3") (pintype "passive"))
      (node (ref "SW08") (pin "4") (pinfunction "4_4") (pintype "passive"))
    )
    (net (code "82") (name "Net-(IC6-I{slash}O0.1)") (class "Default")
      (node (ref "IC6") (pin "5") (pinfunction "I/O0.1_5") (pintype "bidirectional"))
      (node (ref "SW07") (pin "3") (pinfunction "3_3") (pintype "passive"))
      (node (ref "SW07") (pin "4") (pinfunction "4_4") (pintype "passive"))
    )
    (net (code "83") (name "Net-(IC6-I{slash}O0.2)") (class "Default")
      (node (ref "IC6") (pin "6") (pinfunction "I/O0.2_6") (pintype "bidirectional"))
      (node (ref "SW06") (pin "3") (pinfunction "3_3") (pintype "passive"))
      (node (ref "SW06") (pin "4") (pinfunction "4_4") (pintype "passive"))
    )
    (net (code "84") (name "Net-(IC6-I{slash}O0.3)") (class "Default")
      (node (ref "IC6") (pin "7") (pinfunction "I/O0.3_7") (pintype "bidirectional"))
      (node (ref "SW05") (pin "3") (pinfunction "3_3") (pintype "passive"))
      (node (ref "SW05") (pin "4") (pinfunction "4_4") (pintype "passive"))
    )
    (net (code "85") (name "Net-(IC6-I{slash}O0.4)") (class "Default")
      (node (ref "IC6") (pin "8") (pinfunction "I/O0.4_8") (pintype "bidirectional"))
      (node (ref "SW04") (pin "3") (pinfunction "3_3") (pintype "passive"))
      (node (ref "SW04") (pin "4") (pinfunction "4_4") (pintype "passive"))
    )
    (net (code "86") (name "Net-(IC6-I{slash}O0.5)") (class "Default")
      (node (ref "IC6") (pin "9") (pinfunction "I/O0.5_9") (pintype "bidirectional"))
      (node (ref "SW03") (pin "3") (pinfunction "3_3") (pintype "passive"))
      (node (ref "SW03") (pin "4") (pinfunction "4_4") (pintype "passive"))
    )
    (net (code "87") (name "Net-(IC6-I{slash}O0.6)") (class "Default")
      (node (ref "IC6") (pin "10") (pinfunction "I/O0.6_10") (pintype "bidirectional"))
      (node (ref "SW02") (pin "3") (pinfunction "3_3") (pintype "passive"))
      (node (ref "SW02") (pin "4") (pinfunction "4_4") (pintype "passive"))
    )
    (net (code "88") (name "Net-(IC6-I{slash}O1.0)") (class "Default")
      (node (ref "IC6") (pin "13") (pinfunction "I/O1.0_13") (pintype "bidirectional"))
      (node (ref "SW09") (pin "3") (pinfunction "3_3") (pintype "passive"))
      (node (ref "SW09") (pin "4") (pinfunction "4_4") (pintype "passive"))
    )
    (net (code "89") (name "Net-(IC6-I{slash}O1.1)") (class "Default")
      (node (ref "IC6") (pin "14") (pinfunction "I/O1.1_14") (pintype "bidirectional"))
      (node (ref "R8") (pin "1") (pinfunction "1_1") (pintype "passive"))
      (node (ref "R9") (pin "2") (pinfunction "2_2") (pintype "passive"))
    )
    (net (code "90") (name "Net-(IC6-I{slash}O1.2)") (class "Default")
      (node (ref "IC6") (pin "15") (pinfunction "I/O1.2_15") (pintype "bidirectional"))
      (node (ref "SW10") (pin "3") (pinfunction "3_3") (pintype "passive"))
      (node (ref "SW10") (pin "4") (pinfunction "4_4") (pintype "passive"))
    )
    (net (code "91") (name "Net-(IC6-I{slash}O1.3)") (class "Default")
      (node (ref "IC6") (pin "16") (pinfunction "I/O1.3_16") (pintype "bidirectional"))
      (node (ref "SW11") (pin "3") (pinfunction "3_3") (pintype "passive"))
      (node (ref "SW11") (pin "4") (pinfunction "4_4") (pintype "passive"))
    )
    (net (code "92") (name "Net-(IC6-I{slash}O1.4)") (class "Default")
      (node (ref "IC6") (pin "17") (pinfunction "I/O1.4_17") (pintype "bidirectional"))
      (node (ref "SW12") (pin "3") (pinfunction "3_3") (pintype "passive"))
      (node (ref "SW12") (pin "4") (pinfunction "4_4") (pintype "passive"))
    )
    (net (code "93") (name "Net-(IC8-BP0)") (class "Default")
      (node (ref "DISPLAY1") (pin "COM1") (pinfunction "COM1_COM1") (pintype "input"))
      (node (ref "IC8") (pin "25") (pinfunction "BP0_25") (pintype "output"))
    )
    (net (code "94") (name "Net-(IC8-BP1)") (class "Default")
      (node (ref "DISPLAY1") (pin "COM2") (pinfunction "COM2_COM2") (pintype "input"))
      (node (ref "IC8") (pin "26") (pinfunction "BP1_26") (pintype "output"))
    )
    (net (code "95") (name "Net-(IC8-BP2)") (class "Default")
      (node (ref "DISPLAY1") (pin "COM3") (pinfunction "COM3_COM3") (pintype "input"))
      (node (ref "IC8") (pin "27") (pinfunction "BP2_27") (pintype "output"))
    )
    (net (code "96") (name "Net-(IC8-S0)") (class "Default")
      (node (ref "DISPLAY1") (pin "SEG01") (pinfunction "SEG01_SEG01") (pintype "input"))
      (node (ref "IC8") (pin "29") (pinfunction "S0_29") (pintype "output"))
    )
    (net (code "97") (name "Net-(IC8-S1)") (class "Default")
      (node (ref "DISPLAY1") (pin "SEG02") (pinfunction "SEG02_SEG02") (pintype "input"))
      (node (ref "IC8") (pin "30") (pinfunction "S1_30") (pintype "output"))
    )
    (net (code "98") (name "Net-(IC8-S2)") (class "Default")
      (node (ref "DISPLAY1") (pin "SEG03") (pinfunction "SEG03_SEG03") (pintype "input"))
      (node (ref "IC8") (pin "31") (pinfunction "S2_31") (pintype "output"))
    )
    (net (code "99") (name "Net-(IC8-S3)") (class "Default")
      (node (ref "DISPLAY1") (pin "SEG04") (pinfunction "SEG04_SEG04") (pintype "input"))
      (node (ref "IC8") (pin "32") (pinfunction "S3_32") (pintype "output"))
    )
    (net (code "100") (name "Net-(IC8-S4)") (class "Default")
      (node (ref "DISPLAY1") (pin "SEG05") (pinfunction "SEG05_SEG05") (pintype "input"))
      (node (ref "IC8") (pin "34") (pinfunction "S4_34") (pintype "output"))
    )
    (net (code "101") (name "Net-(IC8-S5)") (class "Default")
      (node (ref "DISPLAY1") (pin "SEG06") (pinfunction "SEG06_SEG06") (pintype "input"))
      (node (ref "IC8") (pin "35") (pinfunction "S5_35") (pintype "output"))
    )
    (net (code "102") (name "Net-(IC8-S6)") (class "Default")
      (node (ref "DISPLAY1") (pin "SEG07") (pinfunction "SEG07_SEG07") (pintype "input"))
      (node (ref "IC8") (pin "36") (pinfunction "S6_36") (pintype "output"))
    )
    (net (code "103") (name "Net-(IC8-S7)") (class "Default")
      (node (ref "DISPLAY1") (pin "SEG08") (pinfunction "SEG08_SEG08") (pintype "input"))
      (node (ref "IC8") (pin "37") (pinfunction "S7_37") (pintype "output"))
    )
    (net (code "104") (name "Net-(IC8-S8)") (class "Default")
      (node (ref "DISPLAY1") (pin "SEG09") (pinfunction "SEG09_SEG09") (pintype "input"))
      (node (ref "IC8") (pin "38") (pinfunction "S8_38") (pintype "output"))
    )
    (net (code "105") (name "Net-(IC8-S9)") (class "Default")
      (node (ref "DISPLAY1") (pin "SEG10") (pinfunction "SEG10_SEG10") (pintype "input"))
      (node (ref "IC8") (pin "39") (pinfunction "S9_39") (pintype "output"))
    )
    (net (code "106") (name "Net-(IC8-S10)") (class "Default")
      (node (ref "DISPLAY1") (pin "SEG11") (pinfunction "SEG11_SEG11") (pintype "input"))
      (node (ref "IC8") (pin "40") (pinfunction "S10_40") (pintype "output"))
    )
    (net (code "107") (name "Net-(IC8-S11)") (class "Default")
      (node (ref "DISPLAY1") (pin "SEG12") (pinfunction "SEG12_SEG12") (pintype "input"))
      (node (ref "IC8") (pin "41") (pinfunction "S11_41") (pintype "output"))
    )
    (net (code "108") (name "Net-(IC8-S12)") (class "Default")
      (node (ref "DISPLAY1") (pin "SEG13") (pinfunction "SEG13_SEG13") (pintype "input"))
      (node (ref "IC8") (pin "42") (pinfunction "S12_42") (pintype "output"))
    )
    (net (code "109") (name "Net-(IC8-S13)") (class "Default")
      (node (ref "DISPLAY1") (pin "SEG14") (pinfunction "SEG14_SEG14") (pintype "input"))
      (node (ref "IC8") (pin "43") (pinfunction "S13_43") (pintype "output"))
    )
    (net (code "110") (name "Net-(IC8-S14)") (class "Default")
      (node (ref "DISPLAY1") (pin "SEG15") (pinfunction "SEG15_SEG15") (pintype "input"))
      (node (ref "IC8") (pin "44") (pinfunction "S14_44") (pintype "output"))
    )
    (net (code "111") (name "Net-(IC8-S15)") (class "Default")
      (node (ref "DISPLAY1") (pin "SEG16") (pinfunction "SEG16_SEG16") (pintype "input"))
      (node (ref "IC8") (pin "45") (pinfunction "S15_45") (pintype "output"))
    )
    (net (code "112") (name "Net-(IC8-S16)") (class "Default")
      (node (ref "DISPLAY1") (pin "SEG17") (pinfunction "SEG17_SEG17") (pintype "input"))
      (node (ref "IC8") (pin "46") (pinfunction "S16_46") (pintype "output"))
    )
    (net (code "113") (name "Net-(IC8-S17)") (class "Default")
      (node (ref "DISPLAY1") (pin "SEG18") (pinfunction "SEG18_SEG18") (pintype "input"))
      (node (ref "IC8") (pin "47") (pinfunction "S17_47") (pintype "output"))
    )
    (net (code "114") (name "Net-(IC8-S18)") (class "Default")
      (node (ref "DISPLAY1") (pin "SEG19") (pinfunction "SEG19_SEG19") (pintype "input"))
      (node (ref "IC8") (pin "49") (pinfunction "S18_49") (pintype "output"))
    )
    (net (code "115") (name "Net-(IC8-S19)") (class "Default")
      (node (ref "DISPLAY1") (pin "SEG20") (pinfunction "SEG20_SEG20") (pintype "input"))
      (node (ref "IC8") (pin "50") (pinfunction "S19_50") (pintype "output"))
    )
    (net (code "116") (name "Net-(IC8-S20)") (class "Default")
      (node (ref "DISPLAY1") (pin "SEG21") (pinfunction "SEG21_SEG21") (pintype "input"))
      (node (ref "IC8") (pin "51") (pinfunction "S20_51") (pintype "output"))
    )
    (net (code "117") (name "Net-(IC8-S21)") (class "Default")
      (node (ref "DISPLAY1") (pin "SEG22") (pinfunction "SEG22_SEG22") (pintype "input"))
      (node (ref "IC8") (pin "52") (pinfunction "S21_52") (pintype "output"))
    )
    (net (code "118") (name "Net-(IC8-S22)") (class "Default")
      (node (ref "DISPLAY1") (pin "SEG23") (pinfunction "SEG23_SEG23") (pintype "input"))
      (node (ref "IC8") (pin "53") (pinfunction "S22_53") (pintype "output"))
    )
    (net (code "119") (name "Net-(IC8-S23)") (class "Default")
      (node (ref "DISPLAY1") (pin "SEG24") (pinfunction "SEG24_SEG24") (pintype "input"))
      (node (ref "IC8") (pin "54") (pinfunction "S23_54") (pintype "output"))
    )
    (net (code "120") (name "Net-(IC8-S24)") (class "Default")
      (node (ref "DISPLAY1") (pin "SEG25") (pinfunction "SEG25_SEG25") (pintype "input"))
      (node (ref "IC8") (pin "55") (pinfunction "S24_55") (pintype "output"))
    )
    (net (code "121") (name "Net-(IC8-S25)") (class "Default")
      (node (ref "DISPLAY1") (pin "SEG26") (pinfunction "SEG26_SEG26") (pintype "input"))
      (node (ref "IC8") (pin "56") (pinfunction "S25_56") (pintype "output"))
    )
    (net (code "122") (name "Net-(IC8-S26)") (class "Default")
      (node (ref "DISPLAY1") (pin "SEG27") (pinfunction "SEG27_SEG27") (pintype "input"))
      (node (ref "IC8") (pin "57") (pinfunction "S26_57") (pintype "output"))
    )
    (net (code "123") (name "Net-(IC8-S27)") (class "Default")
      (node (ref "DISPLAY1") (pin "SEG28") (pinfunction "SEG28_SEG28") (pintype "input"))
      (node (ref "IC8") (pin "58") (pinfunction "S27_58") (pintype "output"))
    )
    (net (code "124") (name "Net-(IC8-S28)") (class "Default")
      (node (ref "DISPLAY1") (pin "SEG29") (pinfunction "SEG29_SEG29") (pintype "input"))
      (node (ref "IC8") (pin "59") (pinfunction "S28_59") (pintype "output"))
    )
    (net (code "125") (name "Net-(IC8-S29)") (class "Default")
      (node (ref "DISPLAY1") (pin "SEG30") (pinfunction "SEG30_SEG30") (pintype "input"))
      (node (ref "IC8") (pin "60") (pinfunction "S29_60") (pintype "output"))
    )
    (net (code "126") (name "Net-(IC8-S30)") (class "Default")
      (node (ref "DISPLAY1") (pin "SEG31") (pinfunction "SEG31_SEG31") (pintype "input"))
      (node (ref "IC8") (pin "61") (pinfunction "S30_61") (pintype "output"))
    )
    (net (code "127") (name "Net-(IC8-S31)") (class "Default")
      (node (ref "DISPLAY1") (pin "SEG32") (pinfunction "SEG32_SEG32") (pintype "input"))
      (node (ref "IC8") (pin "62") (pinfunction "S31_62") (pintype "output"))
    )
    (net (code "128") (name "Net-(IC8-S32)") (class "Default")
      (node (ref "DISPLAY1") (pin "SEG33") (pinfunction "SEG33_SEG33") (pintype "input"))
      (node (ref "IC8") (pin "63") (pinfunction "S32_63") (pintype "output"))
    )
    (net (code "129") (name "Net-(IC8-VLCD)") (class "Default")
      (node (ref "IC8") (pin "21") (pinfunction "VLCD_21") (pintype "power_in"))
      (node (ref "R30") (pin "2") (pinfunction "2_2") (pintype "passive"))
    )
    (net (code "130") (name "Net-(R1-Pad1)") (class "Default")
      (node (ref "R1") (pin "1") (pinfunction "1_1") (pintype "passive"))
      (node (ref "T6") (pin "B") (pinfunction "B_B") (pintype "passive"))
    )
    (net (code "131") (name "Net-(R7-Pad2)") (class "Default")
      (node (ref "R7") (pin "2") (pinfunction "2_2") (pintype "passive"))
      (node (ref "U2") (pin "8") (pinfunction "8_8") (pintype "passive"))
    )
    (net (code "132") (name "Net-(R11-Pad1)") (class "Default")
      (node (ref "R11") (pin "1") (pinfunction "1_1") (pintype "passive"))
      (node (ref "T5") (pin "B") (pinfunction "B_B") (pintype "passive"))
    )
    (net (code "133") (name "Net-(R24-S)") (class "Default")
      (node (ref "R24") (pin "2") (pinfunction "S_2") (pintype "passive"))
      (node (ref "R28") (pin "1") (pinfunction "1_1") (pintype "passive"))
    )
    (net (code "134") (name "Net-(RF-POWER-S)") (class "Default")
      (node (ref "RF-POWER") (pin "2") (pinfunction "S_2") (pintype "passive"))
      (node (ref "U2") (pin "6") (pinfunction "6_6") (pintype "passive"))
    )
    (net (code "135") (name "Net-(SQUELCH-A)") (class "Default")
      (node (ref "R2") (pin "1") (pinfunction "1_1") (pintype "passive"))
      (node (ref "SQUELCH") (pin "3") (pinfunction "A_3") (pintype "passive"))
    )
    (net (code "136") (name "Net-(SQUELCH-S)") (class "Default")
      (node (ref "SQUELCH") (pin "2") (pinfunction "S_2") (pintype "passive"))
      (node (ref "U2") (pin "4") (pinfunction "4_4") (pintype "passive"))
    )
    (net (code "137") (name "Net-(SWR/CAL-S)") (class "Default")
      (node (ref "R7") (pin "1") (pinfunction "1_1") (pintype "passive"))
      (node (ref "SWR/CAL") (pin "2") (pinfunction "S_2") (pintype "passive"))
    )
    (net (code "138") (name "Net-(T1-B)") (class "Default")
      (node (ref "R12") (pin "2") (pinfunction "2_2") (pintype "passive"))
      (node (ref "T1") (pin "1") (pinfunction "B_1") (pintype "passive"))
    )
    (net (code "139") (name "Net-(T1-C)") (class "Default")
      (node (ref "T1") (pin "4") (pinfunction "C_4") (pintype "passive"))
      (node (ref "U1") (pin "3") (pinfunction "3_3") (pintype "passive"))
    )
    (net (code "140") (name "Net-(T2-B)") (class "Default")
      (node (ref "R14") (pin "1") (pinfunction "1_1") (pintype "passive"))
      (node (ref "T2") (pin "1") (pinfunction "B_1") (pintype "passive"))
    )
    (net (code "141") (name "Net-(T3-B)") (class "Default")
      (node (ref "R16") (pin "1") (pinfunction "1_1") (pintype "passive"))
      (node (ref "T3") (pin "1") (pinfunction "B_1") (pintype "passive"))
    )
    (net (code "142") (name "Net-(T4-B)") (class "Default")
      (node (ref "R15") (pin "1") (pinfunction "1_1") (pintype "passive"))
      (node (ref "T4") (pin "1") (pinfunction "B_1") (pintype "passive"))
    )
    (net (code "143") (name "Net-(T4-C)") (class "Default")
      (node (ref "R32") (pin "2") (pinfunction "2_2") (pintype "passive"))
      (node (ref "T4") (pin "4") (pinfunction "C_4") (pintype "passive"))
    )
    (net (code "144") (name "Net-(VOLUME-A)") (class "Default")
      (node (ref "U2") (pin "3") (pinfunction "3_3") (pintype "passive"))
      (node (ref "VOLUME") (pin "3") (pinfunction "A_3") (pintype "passive"))
    )
    (net (code "145") (name "Net-(VOLUME-E)") (class "Default")
      (node (ref "U2") (pin "2") (pinfunction "2_2") (pintype "passive"))
      (node (ref "VOLUME") (pin "1") (pinfunction "E_1") (pintype "passive"))
    )
    (net (code "146") (name "Net-(VOLUME-S)") (class "Default")
      (node (ref "U2") (pin "1") (pinfunction "1_1") (pintype "passive"))
      (node (ref "VOLUME") (pin "2") (pinfunction "S_2") (pintype "passive"))
    )
    (net (code "147") (name "VCC") (class "Default")
      (node (ref "5V") (pin "MP") (pinfunction "MP_MP") (pintype "passive"))
      (node (ref "C13") (pin "2") (pinfunction "2_2") (pintype "passive"))
      (node (ref "C17") (pin "2") (pinfunction "2_2") (pintype "passive"))
      (node (ref "C23") (pin "2") (pinfunction "2_2") (pintype "passive"))
      (node (ref "C24") (pin "2") (pinfunction "2_2") (pintype "passive"))
      (node (ref "C4") (pin "+") (pinfunction "+_+") (pintype "passive"))
      (node (ref "D2") (pin "C") (pinfunction "C_C") (pintype "passive"))
      (node (ref "IC3") (pin "28") (pinfunction "VCC_28") (pintype "bidirectional"))
      (node (ref "IC5") (pin "21") (pinfunction "A0_21") (pintype "input"))
      (node (ref "IC5") (pin "24") (pinfunction "VDD_24") (pintype "power_in"))
      (node (ref "IC6") (pin "24") (pinfunction "VDD_24") (pintype "power_in"))
      (node (ref "IC8") (pin "14") (pinfunction "VDD_14") (pintype "power_in"))
      (node (ref "R13") (pin "1") (pinfunction "1_1") (pintype "passive"))
      (node (ref "R21") (pin "1") (pinfunction "1_1") (pintype "passive"))
      (node (ref "R22") (pin "1") (pinfunction "1_1") (pintype "passive"))
      (node (ref "R26") (pin "2") (pinfunction "2_2") (pintype "passive"))
      (node (ref "R27") (pin "2") (pinfunction "2_2") (pintype "passive"))
      (node (ref "R9") (pin "1") (pinfunction "1_1") (pintype "passive"))
    )
    (net (code "148") (name "VCCMEM") (class "Default")
      (node (ref "C16") (pin "2") (pinfunction "2_2") (pintype "passive"))
      (node (ref "C8") (pin "2") (pinfunction "2_2") (pintype "passive"))
      (node (ref "D1") (pin "C") (pinfunction "C_C") (pintype "passive"))
      (node (ref "GC+") (pin "MP") (pinfunction "MP_MP") (pintype "passive"))
      (node (ref "IC1") (pin "21") (pinfunction "VCC_21") (pintype "power_in"))
      (node (ref "IC1") (pin "52") (pinfunction "VCC_52") (pintype "power_in"))
      (node (ref "IC7") (pin "3") (pinfunction "~{WP}_3") (pintype "input"))
      (node (ref "IC7") (pin "7") (pinfunction "~{HOLD}_7") (pintype "input"))
      (node (ref "IC7") (pin "8") (pinfunction "VCC_8") (pintype "power_in"))
      (node (ref "L1") (pin "2") (pinfunction "2_2") (pintype "passive"))
    )
    (net (code "149") (name "unconnected-(IC1-(A10)PC2-Pad37)") (class "Default")
      (node (ref "IC1") (pin "37") (pinfunction "(A10)PC2_37") (pintype "output"))
    )
    (net (code "150") (name "unconnected-(IC1-(A14)PC6-Pad41)") (class "Default")
      (node (ref "IC1") (pin "41") (pinfunction "(A14)PC6_41") (pintype "output"))
    )
    (net (code "151") (name "unconnected-(IC1-(A15)PC7-Pad42)") (class "Default")
      (node (ref "IC1") (pin "42") (pinfunction "(A15)PC7_42") (pintype "output"))
    )
    (net (code "152") (name "unconnected-(IC1-(AD0)PA0-Pad51)") (class "Default")
      (node (ref "IC1") (pin "51") (pinfunction "(AD0)PA0_51") (pintype "bidirectional"))
    )
    (net (code "153") (name "unconnected-(IC1-(AD1)PA1-Pad50)") (class "Default")
      (node (ref "IC1") (pin "50") (pinfunction "(AD1)PA1_50") (pintype "bidirectional"))
    )
    (net (code "154") (name "unconnected-(IC1-(IC1)PD4-Pad29)") (class "Default")
      (node (ref "IC1") (pin "29") (pinfunction "(IC1)PD4_29") (pintype "bidirectional"))
    )
    (net (code "155") (name "unconnected-(IC1-(OC0)PB4-Pad14)") (class "Default")
      (node (ref "IC1") (pin "14") (pinfunction "(OC0)PB4_14") (pintype "bidirectional"))
    )
    (net (code "156") (name "unconnected-(IC1-(OC1B)PB6-Pad16)") (class "Default")
      (node (ref "IC1") (pin "16") (pinfunction "(OC1B)PB6_16") (pintype "bidirectional"))
    )
    (net (code "157") (name "unconnected-(IC1-(OC2{slash}OC1C)PB7-Pad17)") (class "Default")
      (node (ref "IC1") (pin "17") (pinfunction "(OC2/OC1C)PB7_17") (pintype "bidirectional"))
    )
    (net (code "158") (name "unconnected-(IC1-(T1)PD6-Pad31)") (class "Default")
      (node (ref "IC1") (pin "31") (pinfunction "(T1)PD6_31") (pintype "bidirectional"))
    )
    (net (code "159") (name "unconnected-(IC1-(T2)PD7-Pad32)") (class "Default")
      (node (ref "IC1") (pin "32") (pinfunction "(T2)PD7_32") (pintype "bidirectional"))
    )
    (net (code "160") (name "unconnected-(IC1-(XCK0{slash}AIN0)PE2-Pad4)") (class "Default")
      (node (ref "IC1") (pin "4") (pinfunction "(XCK0/AIN0)PE2_4") (pintype "bidirectional"))
    )
    (net (code "161") (name "unconnected-(IC1-(XCK1)PD5-Pad30)") (class "Default")
      (node (ref "IC1") (pin "30") (pinfunction "(XCK1)PD5_30") (pintype "bidirectional"))
    )
    (net (code "162") (name "unconnected-(IC1-AREF-Pad62)") (class "Default")
      (node (ref "IC1") (pin "62") (pinfunction "AREF_62") (pintype "passive"))
    )
    (net (code "163") (name "unconnected-(IC1-PEN-Pad1)") (class "Default")
      (node (ref "IC1") (pin "1") (pinfunction "PEN_1") (pintype "input"))
    )
    (net (code "164") (name "unconnected-(IC1-PF2(ADC2)-Pad59)") (class "Default")
      (node (ref "IC1") (pin "59") (pinfunction "PF2(ADC2)_59") (pintype "input"))
    )
    (net (code "165") (name "unconnected-(IC1-PF3(ADC3)-Pad58)") (class "Default")
      (node (ref "IC1") (pin "58") (pinfunction "PF3(ADC3)_58") (pintype "input"))
    )
    (net (code "166") (name "unconnected-(IC1-PF4(ADC4{slash}TCK)-Pad57)") (class "Default")
      (node (ref "IC1") (pin "57") (pinfunction "PF4(ADC4/TCK)_57") (pintype "input"))
    )
    (net (code "167") (name "unconnected-(IC1-PF5(ADC5{slash}TMS)-Pad56)") (class "Default")
      (node (ref "IC1") (pin "56") (pinfunction "PF5(ADC5/TMS)_56") (pintype "input"))
    )
    (net (code "168") (name "unconnected-(IC1-PF6(ADC6{slash}TDO)-Pad55)") (class "Default")
      (node (ref "IC1") (pin "55") (pinfunction "PF6(ADC6/TDO)_55") (pintype "input"))
    )
    (net (code "169") (name "unconnected-(IC1-PF7(ADC7{slash}TDI)-Pad54)") (class "Default")
      (node (ref "IC1") (pin "54") (pinfunction "PF7(ADC7/TDI)_54") (pintype "input"))
    )
    (net (code "170") (name "unconnected-(IC1-PG0(WR)-Pad33)") (class "Default")
      (node (ref "IC1") (pin "33") (pinfunction "PG0(WR)_33") (pintype "bidirectional"))
    )
    (net (code "171") (name "unconnected-(IC1-PG1(RD)-Pad34)") (class "Default")
      (node (ref "IC1") (pin "34") (pinfunction "PG1(RD)_34") (pintype "bidirectional"))
    )
    (net (code "172") (name "unconnected-(IC1-PG2(ALE)-Pad43)") (class "Default")
      (node (ref "IC1") (pin "43") (pinfunction "PG2(ALE)_43") (pintype "bidirectional"))
    )
    (net (code "173") (name "unconnected-(IC1-PG3(TOSC2)-Pad18)") (class "Default")
      (node (ref "IC1") (pin "18") (pinfunction "PG3(TOSC2)_18") (pintype "bidirectional"))
    )
    (net (code "174") (name "unconnected-(IC1-PG4(TOSC1)-Pad19)") (class "Default")
      (node (ref "IC1") (pin "19") (pinfunction "PG4(TOSC1)_19") (pintype "bidirectional"))
    )
    (net (code "175") (name "unconnected-(IC3-{slash}OUT12-Pad20)") (class "Default")
      (node (ref "IC3") (pin "20") (pinfunction "/OUT12_20") (pintype "bidirectional"))
    )
    (net (code "176") (name "unconnected-(IC3-{slash}OUT13-Pad21)") (class "Default")
      (node (ref "IC3") (pin "21") (pinfunction "/OUT13_21") (pintype "bidirectional"))
    )
    (net (code "177") (name "unconnected-(IC3-{slash}OUT14-Pad22)") (class "Default")
      (node (ref "IC3") (pin "22") (pinfunction "/OUT14_22") (pintype "bidirectional"))
    )
    (net (code "178") (name "unconnected-(IC3-{slash}OUT15-Pad23)") (class "Default")
      (node (ref "IC3") (pin "23") (pinfunction "/OUT15_23") (pintype "bidirectional"))
    )
    (net (code "179") (name "unconnected-(IC5-I{slash}O0.3-Pad7)") (class "Default")
      (node (ref "IC5") (pin "7") (pinfunction "I/O0.3_7") (pintype "bidirectional"))
    )
    (net (code "180") (name "unconnected-(IC5-I{slash}O0.4-Pad8)") (class "Default")
      (node (ref "IC5") (pin "8") (pinfunction "I/O0.4_8") (pintype "bidirectional"))
    )
    (net (code "181") (name "unconnected-(IC5-I{slash}O0.5-Pad9)") (class "Default")
      (node (ref "IC5") (pin "9") (pinfunction "I/O0.5_9") (pintype "bidirectional"))
    )
    (net (code "182") (name "unconnected-(IC6-I{slash}O0.7-Pad11)") (class "Default")
      (node (ref "IC6") (pin "11") (pinfunction "I/O0.7_11") (pintype "bidirectional"))
    )
    (net (code "183") (name "unconnected-(IC6-I{slash}O1.5-Pad18)") (class "Default")
      (node (ref "IC6") (pin "18") (pinfunction "I/O1.5_18") (pintype "bidirectional"))
    )
    (net (code "184") (name "unconnected-(IC6-I{slash}O1.6-Pad19)") (class "Default")
      (node (ref "IC6") (pin "19") (pinfunction "I/O1.6_19") (pintype "bidirectional"))
    )
    (net (code "185") (name "unconnected-(IC6-I{slash}O1.7-Pad20)") (class "Default")
      (node (ref "IC6") (pin "20") (pinfunction "I/O1.7_20") (pintype "bidirectional"))
    )
    (net (code "186") (name "unconnected-(IC8-BP3-Pad28)") (class "Default")
      (node (ref "IC8") (pin "28") (pinfunction "BP3_28") (pintype "output"))
    )
    (net (code "187") (name "unconnected-(IC8-CLK-Pad13)") (class "Default")
      (node (ref "IC8") (pin "13") (pinfunction "CLK_13") (pintype "bidirectional"))
    )
    (net (code "188") (name "unconnected-(IC8-S33-Pad64)") (class "Default")
      (node (ref "IC8") (pin "64") (pinfunction "S33_64") (pintype "output"))
    )
    (net (code "189") (name "unconnected-(IC8-S34-Pad2)") (class "Default")
      (node (ref "IC8") (pin "2") (pinfunction "S34_2") (pintype "output"))
    )
    (net (code "190") (name "unconnected-(IC8-S35-Pad3)") (class "Default")
      (node (ref "IC8") (pin "3") (pinfunction "S35_3") (pintype "output"))
    )
    (net (code "191") (name "unconnected-(IC8-S36-Pad4)") (class "Default")
      (node (ref "IC8") (pin "4") (pinfunction "S36_4") (pintype "output"))
    )
    (net (code "192") (name "unconnected-(IC8-S37-Pad5)") (class "Default")
      (node (ref "IC8") (pin "5") (pinfunction "S37_5") (pintype "output"))
    )
    (net (code "193") (name "unconnected-(IC8-S38-Pad6)") (class "Default")
      (node (ref "IC8") (pin "6") (pinfunction "S38_6") (pintype "output"))
    )
    (net (code "194") (name "unconnected-(IC8-S39-Pad7)") (class "Default")
      (node (ref "IC8") (pin "7") (pinfunction "S39_7") (pintype "output"))
    )
    (net (code "195") (name "unconnected-(IC8-SYNC-Pad12)") (class "Default")
      (node (ref "IC8") (pin "12") (pinfunction "SYNC_12") (pintype "bidirectional"))
    )
    (net (code "196") (name "unconnected-(RF-POWER-A-Pad3)") (class "Default")
      (node (ref "RF-POWER") (pin "3") (pinfunction "A_3") (pintype "passive"))
    )
  )
)
